# Farmduino_b_ta.net
KiCad netlist of a schematic drawn in EAGLE
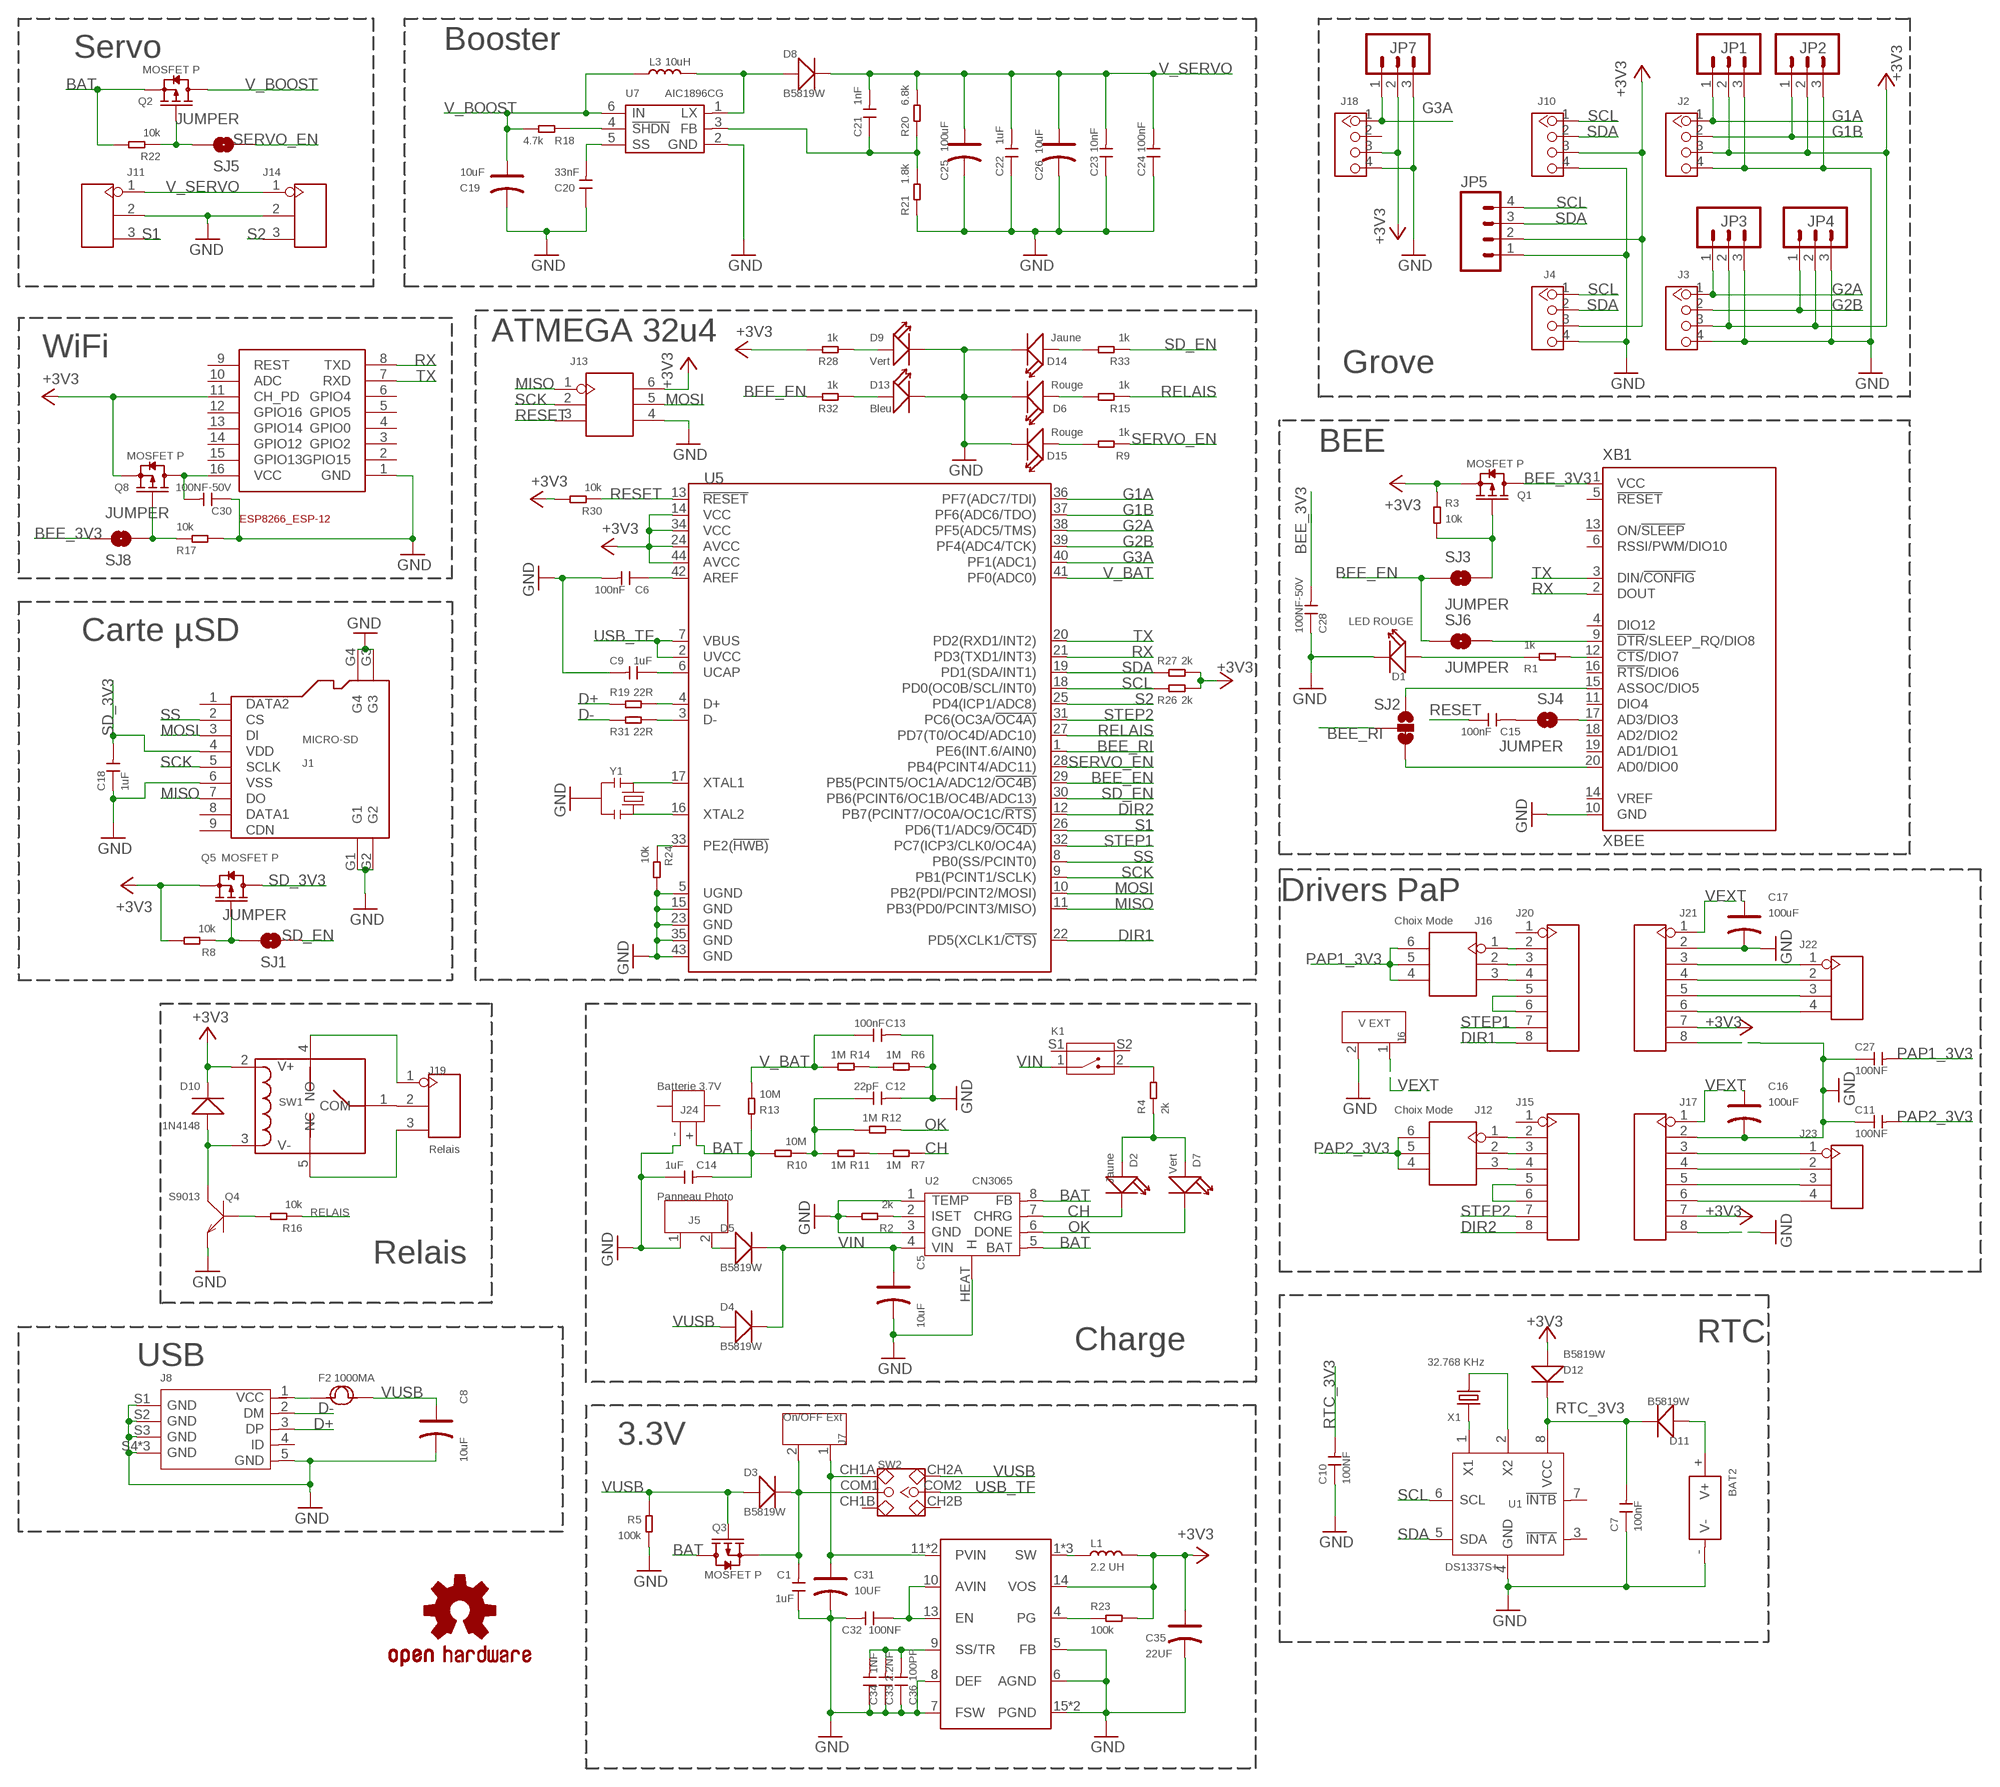
[diagram p0: schematic, sheet 1]

(export (version "E")
  (design (tool "Eeschema 10.0.6"))
  (components
    (comp (ref "BAT2")
      (value "SMD-BATTERY-CELL-HOLDER-PLASTIC")
      (footprint "eagle-import:BAT2P-SMD-16.4-CR1220")
      (libsource (lib "eagle-import") (part "SMD-BATTERY-CELL-HOLDER-PLASTIC"))
    )
    (comp (ref "C1")
      (value "1uF")
      (footprint "eagle-import:C0805")
      (fields
        (field (name "MPN") "CC0805KKX7R8BB105")
        (field (name "MF") "AVX")
        (field (name "MPN_1") "02016D105MAT2A")
      )
      (libsource (lib "eagle-import") (part "CERAMIC-1UF-25V-10%-X7R(0805)"))
    )
    (comp (ref "C5")
      (value "10uF")
      (footprint "eagle-import:AVX-A")
      (fields
        (field (name "MPN") "TAJA106K016RNJ")
        (field (name "MF") "AVX")
        (field (name "MPN_1") "06036D106MAT2A")
      )
      (libsource (lib "eagle-import") (part "TANTALUM-SMD-10UF-16V-10%(AVX-A)"))
    )
    (comp (ref "C6")
      (value "100nF")
      (footprint "eagle-import:C0805")
      (fields
        (field (name "MPN") "CC0805KRX7R9BB104")
        (field (name "MF") "AVX")
        (field (name "MPN_1") "0402ZD104KAT2A")
      )
      (libsource (lib "eagle-import") (part "CERAMIC-100NF-50V-10%-X7R(0805)"))
    )
    (comp (ref "C7")
      (value "100nF")
      (footprint "eagle-import:C0805")
      (fields
        (field (name "MPN") "CC0805KRX7R9BB104")
        (field (name "MF") "AVX")
        (field (name "MPN_1") "0402ZD104KAT2A")
      )
      (libsource (lib "eagle-import") (part "CERAMIC-100NF-50V-10%-X7R(0805)"))
    )
    (comp (ref "C8")
      (value "10uF")
      (footprint "eagle-import:AVX-A")
      (fields
        (field (name "MPN") "TAJA106K016RNJ")
        (field (name "MF") "AVX")
        (field (name "MPN_1") "06036D106MAT2A")
      )
      (libsource (lib "eagle-import") (part "TANTALUM-SMD-10UF-16V-10%(AVX-A)"))
    )
    (comp (ref "C9")
      (value "1uF")
      (footprint "eagle-import:C0805")
      (fields (field (name "MPN") "CC0805KKX7R8BB105") (field (name "MF") "AVX"))
      (libsource (lib "eagle-import") (part "CERAMIC-1UF-25V-10%-X7R(0805)"))
    )
    (comp (ref "C10")
      (value "100NF")
      (footprint "eagle-import:C0805")
      (fields (field (name "MPN") "CC0805KRX7R9BB104"))
      (libsource (lib "eagle-import") (part "CERAMIC-100NF-50V-10%-X7R(0805)"))
    )
    (comp (ref "C11")
      (value "100NF")
      (footprint "eagle-import:C0805")
      (fields (field (name "MPN") "CC0805KRX7R9BB104"))
      (libsource (lib "eagle-import") (part "CERAMIC-100NF-50V-10%-X7R(0805)"))
    )
    (comp (ref "C12")
      (value "22pF")
      (footprint "eagle-import:C0805")
      (fields (field (name "MPN") "CC0805JRNPO9BN220"))
      (libsource (lib "eagle-import") (part "CERAMIC-22PF-50V-5%-NPO(0805)"))
    )
    (comp (ref "C13")
      (value "100nF")
      (footprint "eagle-import:C0805")
      (fields
        (field (name "MPN") "CC0805KRX7R9BB104")
        (field (name "MF") "AVX")
        (field (name "MPN_1") "0402ZD104KAT2A")
      )
      (libsource (lib "eagle-import") (part "CERAMIC-100NF-50V-10%-X7R(0805)"))
    )
    (comp (ref "C14")
      (value "1uF")
      (footprint "eagle-import:C0805")
      (fields
        (field (name "MPN") "CC0805KKX7R8BB105")
        (field (name "MF") "AVX")
        (field (name "MPN_1") "02016D105MAT2A")
      )
      (libsource (lib "eagle-import") (part "CERAMIC-1UF-25V-10%-X7R(0805)"))
    )
    (comp (ref "C15")
      (value "100nF")
      (footprint "eagle-import:C0805")
      (fields
        (field (name "MPN") "CC0805KRX7R9BB104")
        (field (name "MF") "AVX")
        (field (name "MPN_1") "0402ZD104KAT2A")
      )
      (libsource (lib "eagle-import") (part "CERAMIC-100NF-50V-10%-X7R(0805)"))
    )
    (comp (ref "C16")
      (value "100uF")
      (footprint "eagle-import:ELECTRO-SMD-C-6MM")
      (fields
        (field (name "MPN") "CS1H101M-CRE77")
        (field (name "MF") "AVX")
        (field (name "MPN_1") "06036D106MAT2A")
      )
      (libsource (lib "eagle-import") (part "ALUMINUM-SMD-100UF-50V-20%"))
    )
    (comp (ref "C17")
      (value "100uF")
      (footprint "eagle-import:ELECTRO-SMD-C-6MM")
      (fields
        (field (name "MPN") "CS1H101M-CRE77")
        (field (name "MF") "AVX")
        (field (name "MPN_1") "06036D106MAT2A")
      )
      (libsource (lib "eagle-import") (part "ALUMINUM-SMD-100UF-50V-20%"))
    )
    (comp (ref "C18")
      (value "1uF")
      (footprint "eagle-import:C0805")
      (fields
        (field (name "MPN") "CC0805KKX7R8BB105")
        (field (name "MF") "AVX")
        (field (name "MPN_1") "02016D105MAT2A")
      )
      (libsource (lib "eagle-import") (part "CERAMIC-1UF-25V-10%-X7R(0805)"))
    )
    (comp (ref "C19")
      (value "10uF")
      (footprint "eagle-import:AVX-A")
      (fields (field (name "MPN") "TAJA106K010RNJ"))
      (libsource (lib "eagle-import") (part "TANTALUM-SMD-10UF-10V-10%(AVX-A)"))
    )
    (comp (ref "C20")
      (value "33nF")
      (footprint "eagle-import:C0603")
      (fields (field (name "MPN") "CC0603KRX7R9BB333"))
      (libsource (lib "eagle-import") (part "CERAMIC-33NF-50V-10%-X7R(0603)"))
    )
    (comp (ref "C21")
      (value "1nF")
      (footprint "eagle-import:C0603")
      (fields (field (name "MPN") "GRM1885C1H102JA01D"))
      (libsource (lib "eagle-import") (part "CERAMIC-1NF-50V-5%-C0G(0603)"))
    )
    (comp (ref "C22")
      (value "1uF")
      (footprint "eagle-import:C0805")
      (fields
        (field (name "MPN") "CC0805KKX7R8BB105")
        (field (name "MF") "AVX")
        (field (name "MPN_1") "02016D105MAT2A")
      )
      (libsource (lib "eagle-import") (part "CERAMIC-1UF-25V-10%-X7R(0805)"))
    )
    (comp (ref "C23")
      (value "10nF")
      (footprint "eagle-import:C0805")
      (fields (field (name "MPN") "CC0805JRX7R9BB103"))
      (libsource (lib "eagle-import") (part "CERAMIC-10NF-50V-5%-X7R(0805)"))
    )
    (comp (ref "C24")
      (value "100nF")
      (footprint "eagle-import:C0805")
      (fields
        (field (name "MPN") "CC0805KRX7R9BB104")
        (field (name "MF") "AVX")
        (field (name "MPN_1") "0402ZD104KAT2A")
      )
      (libsource (lib "eagle-import") (part "CERAMIC-100NF-50V-10%-X7R(0805)"))
    )
    (comp (ref "C25")
      (value "100uF")
      (footprint "eagle-import:AVX-B")
      (fields (field (name "MPN") "TAJB107M010#NJ"))
      (libsource (lib "eagle-import") (part "TANTALUM-SMD-100UF-10V(AVX-B)"))
    )
    (comp (ref "C26")
      (value "10uF")
      (footprint "eagle-import:AVX-A")
      (fields (field (name "MPN") "TAJA106K016RNJ"))
      (libsource (lib "eagle-import") (part "TANTALUM-SMD-10UF-16V-10%(AVX-A)"))
    )
    (comp (ref "C27")
      (value "100NF")
      (footprint "eagle-import:C0805")
      (fields (field (name "MPN") "CC0805KRX7R9BB104"))
      (libsource (lib "eagle-import") (part "CERAMIC-100NF-50V-10%-X7R(0805)"))
    )
    (comp (ref "C28")
      (value "100NF-50V")
      (footprint "eagle-import:C0805")
      (fields (field (name "MPN") "CC0805KRX7R9BB104"))
      (libsource (lib "eagle-import") (part "CERAMIC-100NF-50V-10%-X7R(0805)"))
    )
    (comp (ref "C30")
      (value "100NF-50V")
      (footprint "eagle-import:C0805")
      (fields (field (name "MPN") "CC0805KRX7R9BB104"))
      (libsource (lib "eagle-import") (part "CERAMIC-100NF-50V-10%-X7R(0805)"))
    )
    (comp (ref "C31")
      (value "10UF")
      (footprint "eagle-import:AVX-A")
      (fields (field (name "MPN") "TAJA106K016RNJ"))
      (libsource (lib "eagle-import") (part "TANTALUM-SMD-10UF-16V-10%(AVX-A)"))
    )
    (comp (ref "C32")
      (value "100NF")
      (footprint "eagle-import:C0805")
      (fields (field (name "MPN") "CC0805KRX7R9BB104"))
      (libsource (lib "eagle-import") (part "CERAMIC-100NF-50V-10%-X7R(0805)"))
    )
    (comp (ref "C33")
      (value "2.2NF")
      (footprint "eagle-import:C0603")
      (fields (field (name "MPN") "CC0603KRX7R9BB222"))
      (libsource (lib "eagle-import") (part "CERAMIC-2.2NF-50V-10%-X7R(0603)"))
    )
    (comp (ref "C34")
      (value "1NF")
      (footprint "eagle-import:C0603")
      (fields (field (name "MPN") "GRM1885C1H102JA01D"))
      (libsource (lib "eagle-import") (part "CERAMIC-1NF-50V-5%-C0G(0603)"))
    )
    (comp (ref "C35")
      (value "22UF")
      (footprint "eagle-import:AVX-B")
      (fields (field (name "MPN") "TAJB226*016#NJ"))
      (libsource (lib "eagle-import") (part "TANTALUM-SMD-22UF-16V(AVX-B)"))
    )
    (comp (ref "C36")
      (value "100PF")
      (footprint "eagle-import:C0603")
      (libsource (lib "eagle-import") (part "CERAMIC-100PF-50V-5%-NPO(0603)"))
    )
    (comp (ref "D1")
      (value "LED ROUGE")
      (footprint "eagle-import:LED-0603")
      (fields (field (name "MPN") "19-217-R6C-AL1M2VY-3T"))
      (libsource (lib "eagle-import") (part "LED-SMD-RED-DIFFUSED(0603)"))
    )
    (comp (ref "D2")
      (value "Jaune")
      (footprint "eagle-import:LED-0805")
      (fields (field (name "MPN") "17-215UYC/S530-A3/TR8"))
      (libsource (lib "eagle-import") (part "SMD-LED-CLEAR-YELLOW(0805)"))
    )
    (comp (ref "D3")
      (value "B5819W")
      (footprint "eagle-import:SOD-123")
      (libsource (lib "eagle-import") (part "SMD-DIODE-SCHOTTKY-20V-1A(SOD-123)"))
    )
    (comp (ref "D4")
      (value "B5819W")
      (footprint "eagle-import:SOD-123")
      (libsource (lib "eagle-import") (part "SMD-DIODE-SCHOTTKY-20V-1A(SOD-123)"))
    )
    (comp (ref "D5")
      (value "B5819W")
      (footprint "eagle-import:SOD-123")
      (libsource (lib "eagle-import") (part "SMD-DIODE-SCHOTTKY-20V-1A(SOD-123)"))
    )
    (comp (ref "D6")
      (value "Rouge")
      (footprint "eagle-import:LED-0603")
      (fields (field (name "MPN") "19-217-R6C-AL1M2VY-3T"))
      (libsource (lib "eagle-import") (part "LED-SMD-RED-DIFFUSED(0603)"))
    )
    (comp (ref "D7")
      (value "Vert")
      (footprint "eagle-import:LED-0805")
      (fields (field (name "MPN") "17-215SYGC/S530-E2/TR8"))
      (libsource (lib "eagle-import") (part "SMD-LED-CLEAR-GREEN(0805)"))
    )
    (comp (ref "D8")
      (value "B5819W")
      (footprint "eagle-import:SOD-123")
      (libsource (lib "eagle-import") (part "SMD-DIODE-SCHOTTKY-20V-1A(SOD-123)"))
    )
    (comp (ref "D9")
      (value "Vert")
      (footprint "eagle-import:LED-0603")
      (fields (field (name "MPN") "19-217-G7C-AN1P2-3T"))
      (libsource (lib "eagle-import") (part "SMD-LED-CLEAR-GREEN(0603)"))
    )
    (comp (ref "D10")
      (value "1N4148")
      (footprint "eagle-import:LL-34")
      (libsource (lib "eagle-import") (part "SMD-DIODE-SWITCH-1N4148(LL-34)"))
    )
    (comp (ref "D11")
      (value "B5819W")
      (footprint "eagle-import:SOD-123")
      (libsource (lib "eagle-import") (part "SMD-DIODE-SCHOTTKY-20V-1A(SOD-123)"))
    )
    (comp (ref "D12")
      (value "B5819W")
      (footprint "eagle-import:SOD-123")
      (libsource (lib "eagle-import") (part "SMD-DIODE-SCHOTTKY-20V-1A(SOD-123)"))
    )
    (comp (ref "D13")
      (value "Bleu")
      (footprint "eagle-import:LED-0603")
      (fields (field (name "MPN") "19-217-BHC-ZL1M2RY-3T"))
      (libsource (lib "eagle-import") (part "SMD-LED-CLEAR-BLUE(0603)"))
    )
    (comp (ref "D14")
      (value "Jaune")
      (footprint "eagle-import:LED-0603")
      (fields (field (name "MPN") "19-217-Y5C-AM1N1VY-3T"))
      (libsource (lib "eagle-import") (part "SMD-LED-CLEAR-YELLOW(0603)"))
    )
    (comp (ref "D15")
      (value "Rouge")
      (footprint "eagle-import:LED-0603")
      (fields (field (name "MPN") "19-217-R6C-AL1M2VY-3T"))
      (libsource (lib "eagle-import") (part "LED-SMD-RED-DIFFUSED(0603)"))
    )
    (comp (ref "F2")
      (value "1000MA")
      (footprint "eagle-import:F1206")
      (fields (field (name "MPN") "KT8-1000SMD1206"))
      (libsource (lib "eagle-import") (part "SMD-PPTC-1000MA-8V(1206)"))
    )
    (comp (ref "J1")
      (value "MICRO-SD")
      (footprint "eagle-import:MICRO-SD9+4P-SMD-16.1X14.5X1.85MM")
      (fields (field (name "MPN") "ST-TF-003A"))
      (libsource (lib "eagle-import") (part "MICRO-SD-CARD-SOCKET-9P(ST-TF-003A)"))
    )
    (comp (ref "J2")
      (value "GROVE-CONNECTOR-DIP(4P-2.0)")
      (footprint "eagle-import:HW4-2.0")
      (libsource (lib "eagle-import") (part "GROVE-CONNECTOR-DIP(4P-2.0)"))
    )
    (comp (ref "J3")
      (value "GROVE-CONNECTOR-DIP(4P-2.0)")
      (footprint "eagle-import:HW4-2.0")
      (libsource (lib "eagle-import") (part "GROVE-CONNECTOR-DIP(4P-2.0)"))
    )
    (comp (ref "J4")
      (value "GROVE-CONNECTOR-DIP(4P-2.0)")
      (footprint "eagle-import:HW4-2.0")
      (libsource (lib "eagle-import") (part "GROVE-CONNECTOR-DIP(4P-2.0)"))
    )
    (comp (ref "J5")
      (value "Panneau Photo")
      (footprint "eagle-import:H2-3.5-7.0X7.0MM")
      (fields (field (name "MF") "TE CONNECTIVITY") (field (name "MPN") "1776275-2"))
      (libsource (lib "eagle-import") (part "SCREW-TERMINAL-GREEN(2P-3.5)"))
    )
    (comp (ref "J6")
      (value "V EXT")
      (footprint "eagle-import:H2-3.5-7.0X7.0MM")
      (fields (field (name "MF") "TE CONNECTIVITY") (field (name "MPN") "1776275-2"))
      (libsource (lib "eagle-import") (part "SCREW-TERMINAL-GREEN(2P-3.5)"))
    )
    (comp (ref "J7")
      (value "On/OFF Ext")
      (footprint "eagle-import:H2-3.5-7.0X7.0MM")
      (libsource (lib "eagle-import") (part "SCREW-TERMINAL-GREEN(2P-3.5)"))
    )
    (comp (ref "J8")
      (value "MICRO-USB-SMD-B-WITHOUT-POST-W/P(ST-USB-001G)")
      (footprint "eagle-import:MICRO-USB5+4P-SMD-0.65-B")
      (fields (field (name "MPN") "ST-USB-001G"))
      (libsource (lib "eagle-import") (part "MICRO-USB-SMD-B-WITHOUT-POST-W/P(ST-USB-001G)"))
    )
    (comp (ref "J10")
      (value "GROVE-CONNECTOR-DIP(4P-2.0)")
      (footprint "eagle-import:HW4-2.0")
      (libsource (lib "eagle-import") (part "GROVE-CONNECTOR-DIP(4P-2.0)"))
    )
    (comp (ref "J11")
      (value "DIP-WHITE-MALE-HEADER-VERT(3P-2.54)")
      (footprint "eagle-import:H3-2.54")
      (fields (field (name "MPN") "P125-1103A0BS116A1"))
      (libsource (lib "eagle-import") (part "DIP-WHITE-MALE-HEADER-VERT(3P-2.54)"))
    )
    (comp (ref "J12")
      (value "Choix Mode")
      (footprint "eagle-import:H2X3-2.54")
      (fields (field (name "MPN") "P125-1203A0BS116A2"))
      (libsource (lib "eagle-import") (part "DIP-YELLOW-MALE-HEADER-VERT(2X3P-2.54)"))
    )
    (comp (ref "J13")
      (value "DIP-BLACK-MALE-HEADER（2X3P-2.54）-2.54")
      (footprint "eagle-import:H2X3-2.54")
      (fields (field (name "MPN") "P125-12A1BS116A1"))
      (libsource (lib "eagle-import") (part "DIP-BLACK-MALE-HEADER（2X3P-2.54）-2.54"))
    )
    (comp (ref "J14")
      (value "DIP-WHITE-MALE-HEADER-VERT(3P-2.54)")
      (footprint "eagle-import:H3-2.54")
      (fields (field (name "MPN") "P125-1103A0BS116A1"))
      (libsource (lib "eagle-import") (part "DIP-WHITE-MALE-HEADER-VERT(3P-2.54)"))
    )
    (comp (ref "J15")
      (value "DIP-YELLOW-FEMALE-HEADER(8P-2.54)")
      (footprint "eagle-import:H8-2.54")
      (fields (field (name "MPN") "F185-1108A1BSYC1"))
      (libsource (lib "eagle-import") (part "DIP-YELLOW-FEMALE-HEADER(8P-2.54)"))
    )
    (comp (ref "J16")
      (value "Choix Mode")
      (footprint "eagle-import:H2X3-2.54")
      (fields (field (name "MPN") "P125-1203A0BS116A2"))
      (libsource (lib "eagle-import") (part "DIP-YELLOW-MALE-HEADER-VERT(2X3P-2.54)"))
    )
    (comp (ref "J17")
      (value "DIP-YELLOW-FEMALE-HEADER(8P-2.54)")
      (footprint "eagle-import:H8-2.54")
      (fields (field (name "MPN") "F185-1108A1BSYC1"))
      (libsource (lib "eagle-import") (part "DIP-YELLOW-FEMALE-HEADER(8P-2.54)"))
    )
    (comp (ref "J18")
      (value "GROVE-CONNECTOR-DIP(4P-2.0)")
      (footprint "eagle-import:HW4-2.0")
      (libsource (lib "eagle-import") (part "GROVE-CONNECTOR-DIP(4P-2.0)"))
    )
    (comp (ref "J19")
      (value "Relais")
      (footprint "eagle-import:H3-5.0-15.5X8.0MM")
      (libsource (lib "eagle-import") (part "SCREW-TERMINAL-GREEN(3P-5.0)"))
    )
    (comp (ref "J20")
      (value "DIP-YELLOW-FEMALE-HEADER(8P-2.54)")
      (footprint "eagle-import:H8-2.54")
      (fields (field (name "MPN") "F185-1108A1BSYC1"))
      (libsource (lib "eagle-import") (part "DIP-YELLOW-FEMALE-HEADER(8P-2.54)"))
    )
    (comp (ref "J21")
      (value "DIP-YELLOW-FEMALE-HEADER(8P-2.54)")
      (footprint "eagle-import:H8-2.54")
      (fields (field (name "MPN") "F185-1108A1BSYC1"))
      (libsource (lib "eagle-import") (part "DIP-YELLOW-FEMALE-HEADER(8P-2.54)"))
    )
    (comp (ref "J22")
      (value "DIP-BLACK-MALE-HEADER-VERT(4P-2.54)")
      (footprint "eagle-import:H4-2.54")
      (fields (field (name "MPN") "P125-1104A0BS116A1"))
      (libsource (lib "eagle-import") (part "DIP-BLACK-MALE-HEADER-VERT(4P-2.54)"))
    )
    (comp (ref "J23")
      (value "DIP-BLACK-MALE-HEADER-VERT(4P-2.54)")
      (footprint "eagle-import:H4-2.54")
      (fields (field (name "MPN") "P125-1104A0BS116A1"))
      (libsource (lib "eagle-import") (part "DIP-BLACK-MALE-HEADER-VERT(4P-2.54)"))
    )
    (comp (ref "J24")
      (value "Batterie 3.7V")
      (footprint "eagle-import:HW2-SMD-1.0-90D")
      (libsource (lib "eagle-import") (part "SMD-JST-2P-1.0-90D"))
    )
    (comp (ref "JP1")
      (value "M03SCREW")
      (footprint "eagle-import:SCREWTERMINAL-3.5MM-3")
      (libsource (lib "eagle-import") (part "M03SCREW"))
    )
    (comp (ref "JP2")
      (value "M03SCREW")
      (footprint "eagle-import:SCREWTERMINAL-3.5MM-3")
      (libsource (lib "eagle-import") (part "M03SCREW"))
    )
    (comp (ref "JP3")
      (value "M03SCREW")
      (footprint "eagle-import:SCREWTERMINAL-3.5MM-3")
      (libsource (lib "eagle-import") (part "M03SCREW"))
    )
    (comp (ref "JP4")
      (value "M03SCREW")
      (footprint "eagle-import:SCREWTERMINAL-3.5MM-3")
      (libsource (lib "eagle-import") (part "M03SCREW"))
    )
    (comp (ref "JP5")
      (value "M04SCREW")
      (footprint "eagle-import:SCREWTERMINAL-3.5MM-4")
      (libsource (lib "eagle-import") (part "M04SCREW"))
    )
    (comp (ref "JP7")
      (value "M03SCREW")
      (footprint "eagle-import:SCREWTERMINAL-3.5MM-3")
      (libsource (lib "eagle-import") (part "M03SCREW"))
    )
    (comp (ref "K1")
      (value "SMD-BUTTON-2+2P")
      (footprint "eagle-import:SW4-SMD-7.0X3.5X3.5MM-90D")
      (fields (field (name "MPN") "TS-1188E"))
      (libsource (lib "eagle-import") (part "SMD-BUTTON-2+2P"))
    )
    (comp (ref "L1")
      (value "2.2 UH")
      (footprint "eagle-import:L0805")
      (fields (field (name "MPN") "LQM2MPN2R2MG0"))
      (libsource (lib "eagle-import") (part "SMD-INDUCTOR-2.2UH-20%-1.2A(0805)"))
    )
    (comp (ref "L3")
      (value "10uH")
      (footprint "eagle-import:L1210")
      (fields (field (name "MPN") "CBC3225T100MR"))
      (libsource (lib "eagle-import") (part "SMD-INDUCTOR-10UH-20%-900MA(L1210)"))
    )
    (comp (ref "LOGO1")
      (value "OSHW-LOGOM")
      (footprint "eagle-import:OSHW-LOGO-M")
      (libsource (lib "eagle-import") (part "OSHW-LOGOM"))
    )
    (comp (ref "Q1")
      (value "MOSFET P")
      (footprint "eagle-import:SOT-23")
      (fields (field (name "MPN") "CJ2305"))
      (libsource (lib "eagle-import") (part "SMD-MOSFET-P-CH-8V-4.1A(SOT-23)"))
    )
    (comp (ref "Q2")
      (value "MOSFET P")
      (footprint "eagle-import:SOT-23")
      (fields (field (name "MPN") "CJ2305"))
      (libsource (lib "eagle-import") (part "SMD-MOSFET-P-CH-8V-4.1A(SOT-23)"))
    )
    (comp (ref "Q3")
      (value "MOSFET P")
      (footprint "eagle-import:SOT-23")
      (fields (field (name "MPN") "CJ2305"))
      (libsource (lib "eagle-import") (part "SMD-MOSFET-P-CH-8V-4.1A(SOT-23)"))
    )
    (comp (ref "Q4")
      (value "S9013")
      (footprint "eagle-import:SOT-23")
      (libsource (lib "eagle-import") (part "SMD-TRANSISTORS-NPN-25V-500MA(SOT-23)"))
    )
    (comp (ref "Q5")
      (value "MOSFET P")
      (footprint "eagle-import:SOT-23")
      (fields (field (name "MPN") "CJ2305"))
      (libsource (lib "eagle-import") (part "SMD-MOSFET-P-CH-8V-4.1A(SOT-23)"))
    )
    (comp (ref "Q8")
      (value "MOSFET P")
      (footprint "eagle-import:SOT-23")
      (fields (field (name "MPN") "CJ2305"))
      (libsource (lib "eagle-import") (part "SMD-MOSFET-P-CH-8V-4.1A(SOT-23)"))
    )
    (comp (ref "R1")
      (value "1k")
      (footprint "eagle-import:R0805")
      (fields (field (name "MPN") "RC0805JR-071KL") (field (name "MF") "STEINBACH AND VOLLMANN"))
      (libsource (lib "eagle-import") (part "SMD-RES-1K-5%-1/8W(0805)"))
    )
    (comp (ref "R2")
      (value "2k")
      (footprint "eagle-import:R0805")
      (fields (field (name "MPN") "RC0805JR-072KL"))
      (libsource (lib "eagle-import") (part "SMD-RES-2K-5%-1/8W(0805)"))
    )
    (comp (ref "R3")
      (value "10k")
      (footprint "eagle-import:R0805")
      (fields (field (name "MPN") "RC0805FR-0710KL") (field (name "MF") "STEINBACH AND VOLLMANN"))
      (libsource (lib "eagle-import") (part "SMD-RES-10K-1%-1/8W(0805)"))
    )
    (comp (ref "R4")
      (value "2k")
      (footprint "eagle-import:R0805")
      (fields (field (name "MPN") "RC0805JR-072KL"))
      (libsource (lib "eagle-import") (part "SMD-RES-2K-5%-1/8W(0805)"))
    )
    (comp (ref "R5")
      (value "100k")
      (footprint "eagle-import:R0805")
      (fields (field (name "MPN") "RC0805FR-07100KL"))
      (libsource (lib "eagle-import") (part "SMD-RES-100K-1%-1/8W(0805)"))
    )
    (comp (ref "R6")
      (value "1M")
      (footprint "eagle-import:R0402")
      (fields (field (name "MPN") "RC0402FR-071ML"))
      (libsource (lib "eagle-import") (part "SMD-RES-1M-1%-1/16W(0402)"))
    )
    (comp (ref "R7")
      (value "1M")
      (footprint "eagle-import:R0402")
      (fields (field (name "MPN") "RC0402FR-071ML"))
      (libsource (lib "eagle-import") (part "SMD-RES-1M-1%-1/16W(0402)"))
    )
    (comp (ref "R8")
      (value "10k")
      (footprint "eagle-import:R0805")
      (fields (field (name "MPN") "RC0805FR-0710KL"))
      (libsource (lib "eagle-import") (part "SMD-RES-10K-1%-1/8W(0805)"))
    )
    (comp (ref "R9")
      (value "1k")
      (footprint "eagle-import:R0805")
      (fields (field (name "MPN") "RC0805JR-071KL") (field (name "MF") "STEINBACH AND VOLLMANN"))
      (libsource (lib "eagle-import") (part "SMD-RES-1K-5%-1/8W(0805)"))
    )
    (comp (ref "R10")
      (value "10M")
      (footprint "eagle-import:R0603")
      (fields (field (name "MPN") "RC0603FR-0710ML"))
      (libsource (lib "eagle-import") (part "SMD-RES-10M-1%-1/10W(0603)"))
    )
    (comp (ref "R11")
      (value "1M")
      (footprint "eagle-import:R0402")
      (fields (field (name "MPN") "RC0402FR-071ML"))
      (libsource (lib "eagle-import") (part "SMD-RES-1M-1%-1/16W(0402)"))
    )
    (comp (ref "R12")
      (value "1M")
      (footprint "eagle-import:R0805")
      (fields (field (name "MPN") "RC0805JR-071ML"))
      (libsource (lib "eagle-import") (part "SMD-RES-1M-5%-1/8W(0805)"))
    )
    (comp (ref "R13")
      (value "10M")
      (footprint "eagle-import:R0603")
      (fields (field (name "MPN") "RC0603FR-0710ML"))
      (libsource (lib "eagle-import") (part "SMD-RES-10M-1%-1/10W(0603)"))
    )
    (comp (ref "R14")
      (value "1M")
      (footprint "eagle-import:R0402")
      (fields (field (name "MPN") "RC0402FR-071ML"))
      (libsource (lib "eagle-import") (part "SMD-RES-1M-1%-1/16W(0402)"))
    )
    (comp (ref "R15")
      (value "1k")
      (footprint "eagle-import:R0805")
      (fields (field (name "MPN") "RC0805JR-071KL") (field (name "MF") "STEINBACH AND VOLLMANN"))
      (libsource (lib "eagle-import") (part "SMD-RES-1K-5%-1/8W(0805)"))
    )
    (comp (ref "R16")
      (value "10k")
      (footprint "eagle-import:R0805")
      (fields (field (name "MPN") "RC0805FR-0710KL"))
      (libsource (lib "eagle-import") (part "SMD-RES-10K-1%-1/8W(0805)"))
    )
    (comp (ref "R17")
      (value "10k")
      (footprint "eagle-import:R0805")
      (fields (field (name "MPN") "RC0805FR-0710KL"))
      (libsource (lib "eagle-import") (part "SMD-RES-10K-1%-1/8W(0805)"))
    )
    (comp (ref "R18")
      (value "4.7k")
      (footprint "eagle-import:R0805")
      (fields (field (name "MPN") "RC0805JR-074K7L"))
      (libsource (lib "eagle-import") (part "SMD-RES-4.7K-5%-1/8W(0805)"))
    )
    (comp (ref "R19")
      (value "22R")
      (footprint "eagle-import:R0805")
      (fields (field (name "MPN") "RC0805JR-0722RL"))
      (libsource (lib "eagle-import") (part "SMD-RES-22R-5%-1/8W(0805)"))
    )
    (comp (ref "R20")
      (value "6.8k")
      (footprint "eagle-import:R0603")
      (fields (field (name "MPN") "RC0805JR-07220KL"))
      (libsource (lib "eagle-import") (part "SMD-RES-6.8K-1%-1/10W(0603)"))
    )
    (comp (ref "R21")
      (value "1.8k")
      (footprint "eagle-import:R0603")
      (fields (field (name "MPN") "RC0603FR-071K8L"))
      (libsource (lib "eagle-import") (part "SMD-RES-1.8K-1%-1/10W(0603)"))
    )
    (comp (ref "R22")
      (value "10k")
      (footprint "eagle-import:R0805")
      (fields (field (name "MPN") "RC0805FR-0710KL"))
      (libsource (lib "eagle-import") (part "SMD-RES-10K-1%-1/8W(0805)"))
    )
    (comp (ref "R23")
      (value "100k")
      (footprint "eagle-import:R0805")
      (fields (field (name "MPN") "RC0805FR-07100KL"))
      (libsource (lib "eagle-import") (part "SMD-RES-100K-1%-1/8W(0805)"))
    )
    (comp (ref "R24")
      (value "10k")
      (footprint "eagle-import:R0805")
      (fields (field (name "MPN") "RC0805FR-0710KL") (field (name "MF") "STEINBACH AND VOLLMANN"))
      (libsource (lib "eagle-import") (part "SMD-RES-10K-1%-1/8W(0805)"))
    )
    (comp (ref "R26")
      (value "2k")
      (footprint "eagle-import:R0603")
      (fields (field (name "MPN") "RC0603JR-072KL"))
      (libsource (lib "eagle-import") (part "SMD-RES-2K-5%-1/10W(0603)"))
    )
    (comp (ref "R27")
      (value "2k")
      (footprint "eagle-import:R0805")
      (fields (field (name "MPN") "RC0805JR-072KL"))
      (libsource (lib "eagle-import") (part "SMD-RES-2K-5%-1/8W(0805)"))
    )
    (comp (ref "R28")
      (value "1k")
      (footprint "eagle-import:R0805")
      (fields (field (name "MPN") "RC0805JR-071KL") (field (name "MF") "STEINBACH AND VOLLMANN"))
      (libsource (lib "eagle-import") (part "SMD-RES-1K-5%-1/8W(0805)"))
    )
    (comp (ref "R30")
      (value "10k")
      (footprint "eagle-import:R0805")
      (fields (field (name "MPN") "RC0805FR-0710KL") (field (name "MF") "STEINBACH AND VOLLMANN"))
      (libsource (lib "eagle-import") (part "SMD-RES-10K-1%-1/8W(0805)"))
    )
    (comp (ref "R31")
      (value "22R")
      (footprint "eagle-import:R0805")
      (fields (field (name "MPN") "RC0805JR-0722RL"))
      (libsource (lib "eagle-import") (part "SMD-RES-22R-5%-1/8W(0805)"))
    )
    (comp (ref "R32")
      (value "1k")
      (footprint "eagle-import:R0805")
      (fields (field (name "MPN") "RC0805JR-071KL") (field (name "MF") "STEINBACH AND VOLLMANN"))
      (libsource (lib "eagle-import") (part "SMD-RES-1K-5%-1/8W(0805)"))
    )
    (comp (ref "R33")
      (value "1k")
      (footprint "eagle-import:R0805")
      (fields (field (name "MPN") "RC0805JR-071KL") (field (name "MF") "STEINBACH AND VOLLMANN"))
      (libsource (lib "eagle-import") (part "SMD-RES-1K-5%-1/8W(0805)"))
    )
    (comp (ref "SJ1")
      (value "JUMPER")
      (footprint "eagle-import:PAD-JUMPER-2-NO_NO_SILK")
      (libsource (lib "eagle-import") (part "JUMPER-PAD-2-NO"))
    )
    (comp (ref "SJ2")
      (value "JUMPER-PAD-3-2OF3_NC_BY_TRACE_LARGE")
      (footprint "eagle-import:PAD-JUMPER-3-2OF3_NC_BY_TRACE_YES_SILK_LARGE")
      (libsource (lib "eagle-import") (part "JUMPER-PAD-3-2OF3_NC_BY_TRACE_LARGE"))
    )
    (comp (ref "SJ3")
      (value "JUMPER")
      (footprint "eagle-import:PAD-JUMPER-2-NO_NO_SILK")
      (libsource (lib "eagle-import") (part "JUMPER-PAD-2-NO"))
    )
    (comp (ref "SJ4")
      (value "JUMPER")
      (footprint "eagle-import:PAD-JUMPER-2-NO_NO_SILK")
      (libsource (lib "eagle-import") (part "JUMPER-PAD-2-NO"))
    )
    (comp (ref "SJ5")
      (value "JUMPER")
      (footprint "eagle-import:PAD-JUMPER-2-NO_NO_SILK")
      (libsource (lib "eagle-import") (part "JUMPER-PAD-2-NO"))
    )
    (comp (ref "SJ6")
      (value "JUMPER")
      (footprint "eagle-import:PAD-JUMPER-2-NO_NO_SILK")
      (libsource (lib "eagle-import") (part "JUMPER-PAD-2-NO"))
    )
    (comp (ref "SJ8")
      (value "JUMPER")
      (footprint "eagle-import:PAD-JUMPER-2-NO_NO_SILK")
      (libsource (lib "eagle-import") (part "JUMPER-PAD-2-NO"))
    )
    (comp (ref "SW1")
      (value "RELAY-HLS8L-DC3V-S-C(5P-19X15MM)")
      (footprint "eagle-import:REY5-19.0X15.0X15.0MM")
      (libsource (lib "eagle-import") (part "RELAY-HLS8L-DC3V-S-C(5P-19X15MM)"))
    )
    (comp (ref "SW2")
      (value "DIP-TOGGLE-SWITCH-2CH-(2X3P-90D)")
      (footprint "eagle-import:SW6-2.54-9.0X3.5X3.2MM-90D")
      (fields (field (name "MPN") "MS-22D18-G2"))
      (libsource (lib "eagle-import") (part "DIP-TOGGLE-SWITCH-2CH-(2X3P-90D)"))
    )
    (comp (ref "U$1")
      (value "ESP8266_ESP-12")
      (footprint "eagle-import:ESP8266-ESP12")
      (libsource (lib "eagle-import") (part "ESP8266_ESP-12"))
    )
    (comp (ref "U1")
      (value "DS1337S+")
      (footprint "eagle-import:SOIC8-1.27-5X4MM")
      (libsource (lib "eagle-import") (part "CLOCK-DS1337S+(SOIC8)"))
    )
    (comp (ref "U2")
      (value "CN3065")
      (footprint "eagle-import:DFN8G-0.5-3X3MM")
      (libsource (lib "eagle-import") (part "PMIC-CN3065(DFN8)"))
    )
    (comp (ref "U3")
      (value "TPS62132RGTR")
      (footprint "eagle-import:QFN16G-0.5-3X3MM")
      (libsource (lib "eagle-import") (part "PMIC-TPS62132RGTR(QFN16)"))
    )
    (comp (ref "U5")
      (value "MCU-ATMEGA32U4(TQFP44)-AU")
      (footprint "eagle-import:TQFP44-0.8-9.6X9.6MM")
      (libsource (lib "eagle-import") (part "MCU-ATMEGA32U4(TQFP44)-AU"))
    )
    (comp (ref "U7")
      (value "AIC1896CG")
      (footprint "eagle-import:SOT-23-6")
      (libsource (lib "eagle-import") (part "PMIC-AIC1896CG(SOT23-6)"))
    )
    (comp (ref "X1")
      (value "32.768 KHz")
      (footprint "eagle-import:X2-SMD-3.2X1.5X0.55MM")
      (fields (field (name "MPN") "FC-135"))
      (libsource (lib "eagle-import") (part "SMD-CRYSTAL-ABS07-32.768KHZ-7PF-20PPM-70K(2P-3.2X1.5MM)"))
    )
    (comp (ref "XB1")
      (value "XBEE")
      (footprint "eagle-import:XBEE")
      (fields (field (name "MPN") "XBP24-Z7UIT-004"))
      (libsource (lib "eagle-import") (part "XBEE"))
    )
    (comp (ref "Y1")
      (value "SMD-CRYSTAL-8MHZ--0.3%-150R(3P-3.6X1.3MM)")
      (footprint "eagle-import:X3-SMD-3.6X1.3X0.8MM")
      (libsource (lib "eagle-import") (part "SMD-CRYSTAL-8MHZ--0.3%-150R(3P-3.6X1.3MM)"))
    )
  )
  (nets
    (net (code "1") (name "+3V3") (class "Default")
      (node (ref "C35") (pin "+") (pinfunction "+_+") (pintype "passive"))
      (node (ref "D10") (pin "C") (pinfunction "-_C") (pintype "passive"))
      (node (ref "D12") (pin "+") (pinfunction "+_+") (pintype "passive"))
      (node (ref "J10") (pin "3") (pinfunction "3_3") (pintype "bidirectional"))
      (node (ref "J13") (pin "6") (pinfunction "6_6") (pintype "bidirectional"))
      (node (ref "J17") (pin "7") (pinfunction "7_7") (pintype "bidirectional"))
      (node (ref "J18") (pin "3") (pinfunction "3_3") (pintype "bidirectional"))
      (node (ref "J2") (pin "3") (pinfunction "3_3") (pintype "bidirectional"))
      (node (ref "J21") (pin "7") (pinfunction "7_7") (pintype "bidirectional"))
      (node (ref "J3") (pin "3") (pinfunction "3_3") (pintype "bidirectional"))
      (node (ref "J4") (pin "3") (pinfunction "3_3") (pintype "bidirectional"))
      (node (ref "JP1") (pin "2") (pinfunction "2_2") (pintype "passive"))
      (node (ref "JP2") (pin "2") (pinfunction "2_2") (pintype "passive"))
      (node (ref "JP3") (pin "2") (pinfunction "2_2") (pintype "passive"))
      (node (ref "JP4") (pin "2") (pinfunction "2_2") (pintype "passive"))
      (node (ref "JP5") (pin "2") (pinfunction "2_2") (pintype "passive"))
      (node (ref "JP7") (pin "2") (pinfunction "2_2") (pintype "passive"))
      (node (ref "L1") (pin "2") (pinfunction "2_2") (pintype "passive"))
      (node (ref "Q1") (pin "2") (pinfunction "S_2") (pintype "passive"))
      (node (ref "Q5") (pin "2") (pinfunction "S_2") (pintype "passive"))
      (node (ref "Q8") (pin "2") (pinfunction "S_2") (pintype "passive"))
      (node (ref "R23") (pin "2") (pinfunction "2_2") (pintype "passive"))
      (node (ref "R26") (pin "1") (pinfunction "1_1") (pintype "passive"))
      (node (ref "R27") (pin "1") (pinfunction "1_1") (pintype "passive"))
      (node (ref "R28") (pin "2") (pinfunction "2_2") (pintype "passive"))
      (node (ref "R3") (pin "1") (pinfunction "1_1") (pintype "passive"))
      (node (ref "R30") (pin "2") (pinfunction "2_2") (pintype "passive"))
      (node (ref "R8") (pin "2") (pinfunction "2_2") (pintype "passive"))
      (node (ref "SW1") (pin "2") (pinfunction "V+_2") (pintype "bidirectional"))
      (node (ref "U$1") (pin "11") (pinfunction "CH_PD_11") (pintype "bidirectional"))
      (node (ref "U3") (pin "14") (pinfunction "VOS_14") (pintype "bidirectional"))
      (node (ref "U5") (pin "14") (pinfunction "VCC_14") (pintype "bidirectional"))
      (node (ref "U5") (pin "24") (pinfunction "AVCC_24") (pintype "bidirectional"))
      (node (ref "U5") (pin "34") (pinfunction "VCC_34") (pintype "bidirectional"))
      (node (ref "U5") (pin "44") (pinfunction "AVCC_44") (pintype "bidirectional"))
    )
    (net (code "2") (name "BAT") (class "Default")
      (node (ref "C14") (pin "2") (pinfunction "2_2") (pintype "passive"))
      (node (ref "J24") (pin "+") (pinfunction "1_+") (pintype "bidirectional"))
      (node (ref "Q2") (pin "2") (pinfunction "S_2") (pintype "passive"))
      (node (ref "Q3") (pin "3") (pinfunction "D_3") (pintype "passive"))
      (node (ref "R10") (pin "2") (pinfunction "2_2") (pintype "passive"))
      (node (ref "R13") (pin "2") (pinfunction "2_2") (pintype "passive"))
      (node (ref "R22") (pin "2") (pinfunction "2_2") (pintype "passive"))
      (node (ref "U2") (pin "5") (pinfunction "BAT_5") (pintype "bidirectional"))
      (node (ref "U2") (pin "8") (pinfunction "FB_8") (pintype "input"))
    )
    (net (code "3") (name "BEE_3V3") (class "Default")
      (node (ref "C28") (pin "2") (pinfunction "2_2") (pintype "passive"))
      (node (ref "Q1") (pin "3") (pinfunction "D_3") (pintype "passive"))
      (node (ref "SJ8") (pin "1") (pinfunction "1_1") (pintype "passive"))
      (node (ref "XB1") (pin "1") (pinfunction "VCC_1") (pintype "power_in"))
    )
    (net (code "4") (name "BEE_EN") (class "Default")
      (node (ref "R32") (pin "2") (pinfunction "2_2") (pintype "passive"))
      (node (ref "SJ3") (pin "1") (pinfunction "1_1") (pintype "passive"))
      (node (ref "SJ6") (pin "1") (pinfunction "1_1") (pintype "passive"))
      (node (ref "U5") (pin "29") (pinfunction "PB5(PCINT5/OC1A/ADC12/~{OC4B})_29") (pintype "bidirectional"))
    )
    (net (code "5") (name "BEE_RI") (class "Default")
      (node (ref "SJ2") (pin "2") (pinfunction "2_2") (pintype "passive"))
      (node (ref "U5") (pin "1") (pinfunction "PE6(INT.6/AIN0)_1") (pintype "bidirectional"))
    )
    (net (code "6") (name "CH") (class "Default")
      (node (ref "D2") (pin "-") (pinfunction "-_-") (pintype "passive"))
      (node (ref "R7") (pin "1") (pinfunction "1_1") (pintype "passive"))
      (node (ref "U2") (pin "7") (pinfunction "CHRG_7") (pintype "bidirectional"))
    )
    (net (code "7") (name "D+") (class "Default")
      (node (ref "J8") (pin "3") (pinfunction "DP_3") (pintype "bidirectional"))
      (node (ref "R19") (pin "1") (pinfunction "1_1") (pintype "passive"))
    )
    (net (code "8") (name "D-") (class "Default")
      (node (ref "J8") (pin "2") (pinfunction "DM_2") (pintype "bidirectional"))
      (node (ref "R31") (pin "1") (pinfunction "1_1") (pintype "passive"))
    )
    (net (code "9") (name "DIR1") (class "Default")
      (node (ref "J20") (pin "8") (pinfunction "8_8") (pintype "bidirectional"))
      (node (ref "U5") (pin "22") (pinfunction "PD5(XCLK1/~{CTS})_22") (pintype "bidirectional"))
    )
    (net (code "10") (name "DIR2") (class "Default")
      (node (ref "J15") (pin "8") (pinfunction "8_8") (pintype "bidirectional"))
      (node (ref "U5") (pin "12") (pinfunction "PB7(PCINT7/OC0A/OC1C/~{RTS})_12") (pintype "bidirectional"))
    )
    (net (code "11") (name "G1A") (class "Default")
      (node (ref "J2") (pin "1") (pinfunction "1_1") (pintype "bidirectional"))
      (node (ref "JP1") (pin "1") (pinfunction "1_1") (pintype "passive"))
      (node (ref "U5") (pin "36") (pinfunction "PF7(ADC7/TDI)_36") (pintype "bidirectional"))
    )
    (net (code "12") (name "G1B") (class "Default")
      (node (ref "J2") (pin "2") (pinfunction "2_2") (pintype "bidirectional"))
      (node (ref "JP2") (pin "1") (pinfunction "1_1") (pintype "passive"))
      (node (ref "U5") (pin "37") (pinfunction "PF6(ADC6/TDO)_37") (pintype "bidirectional"))
    )
    (net (code "13") (name "G2A") (class "Default")
      (node (ref "J3") (pin "1") (pinfunction "1_1") (pintype "bidirectional"))
      (node (ref "JP3") (pin "1") (pinfunction "1_1") (pintype "passive"))
      (node (ref "U5") (pin "38") (pinfunction "PF5(ADC5/TMS)_38") (pintype "bidirectional"))
    )
    (net (code "14") (name "G2B") (class "Default")
      (node (ref "J3") (pin "2") (pinfunction "2_2") (pintype "bidirectional"))
      (node (ref "JP4") (pin "1") (pinfunction "1_1") (pintype "passive"))
      (node (ref "U5") (pin "39") (pinfunction "PF4(ADC4/TCK)_39") (pintype "bidirectional"))
    )
    (net (code "15") (name "G3A") (class "Default")
      (node (ref "J18") (pin "1") (pinfunction "1_1") (pintype "bidirectional"))
      (node (ref "JP7") (pin "1") (pinfunction "1_1") (pintype "passive"))
      (node (ref "U5") (pin "40") (pinfunction "PF1(ADC1)_40") (pintype "bidirectional"))
    )
    (net (code "16") (name "GND") (class "Default")
      (node (ref "BAT2") (pin "-") (pinfunction "V-_-") (pintype "bidirectional"))
      (node (ref "C1") (pin "1") (pinfunction "1_1") (pintype "passive"))
      (node (ref "C10") (pin "1") (pinfunction "1_1") (pintype "passive"))
      (node (ref "C11") (pin "1") (pinfunction "1_1") (pintype "passive"))
      (node (ref "C12") (pin "2") (pinfunction "2_2") (pintype "passive"))
      (node (ref "C13") (pin "2") (pinfunction "2_2") (pintype "passive"))
      (node (ref "C14") (pin "1") (pinfunction "1_1") (pintype "passive"))
      (node (ref "C16") (pin "-") (pinfunction "-_-") (pintype "passive"))
      (node (ref "C17") (pin "-") (pinfunction "-_-") (pintype "passive"))
      (node (ref "C18") (pin "1") (pinfunction "1_1") (pintype "passive"))
      (node (ref "C19") (pin "-") (pinfunction "-_-") (pintype "passive"))
      (node (ref "C20") (pin "1") (pinfunction "1_1") (pintype "passive"))
      (node (ref "C22") (pin "1") (pinfunction "1_1") (pintype "passive"))
      (node (ref "C23") (pin "1") (pinfunction "1_1") (pintype "passive"))
      (node (ref "C24") (pin "1") (pinfunction "1_1") (pintype "passive"))
      (node (ref "C25") (pin "-") (pinfunction "-_-") (pintype "passive"))
      (node (ref "C26") (pin "-") (pinfunction "-_-") (pintype "passive"))
      (node (ref "C27") (pin "1") (pinfunction "1_1") (pintype "passive"))
      (node (ref "C28") (pin "1") (pinfunction "1_1") (pintype "passive"))
      (node (ref "C30") (pin "1") (pinfunction "1_1") (pintype "passive"))
      (node (ref "C31") (pin "-") (pinfunction "-_-") (pintype "passive"))
      (node (ref "C32") (pin "2") (pinfunction "2_2") (pintype "passive"))
      (node (ref "C33") (pin "1") (pinfunction "1_1") (pintype "passive"))
      (node (ref "C34") (pin "1") (pinfunction "1_1") (pintype "passive"))
      (node (ref "C35") (pin "-") (pinfunction "-_-") (pintype "passive"))
      (node (ref "C36") (pin "1") (pinfunction "1_1") (pintype "passive"))
      (node (ref "C5") (pin "-") (pinfunction "-_-") (pintype "passive"))
      (node (ref "C6") (pin "2") (pinfunction "2_2") (pintype "passive"))
      (node (ref "C7") (pin "1") (pinfunction "1_1") (pintype "passive"))
      (node (ref "C8") (pin "-") (pinfunction "-_-") (pintype "passive"))
      (node (ref "C9") (pin "2") (pinfunction "2_2") (pintype "passive"))
      (node (ref "D1") (pin "-") (pinfunction "-_-") (pintype "passive"))
      (node (ref "D13") (pin "-") (pinfunction "-_-") (pintype "passive"))
      (node (ref "D14") (pin "-") (pinfunction "-_-") (pintype "passive"))
      (node (ref "D15") (pin "-") (pinfunction "-_-") (pintype "passive"))
      (node (ref "D6") (pin "-") (pinfunction "-_-") (pintype "passive"))
      (node (ref "D9") (pin "-") (pinfunction "-_-") (pintype "passive"))
      (node (ref "J1") (pin "6") (pinfunction "VSS_6") (pintype "bidirectional"))
      (node (ref "J1") (pin "G1") (pinfunction "G1_G1") (pintype "bidirectional"))
      (node (ref "J1") (pin "G2") (pinfunction "G2_G2") (pintype "bidirectional"))
      (node (ref "J1") (pin "G3") (pinfunction "G3_G3") (pintype "bidirectional"))
      (node (ref "J1") (pin "G4") (pinfunction "G4_G4") (pintype "bidirectional"))
      (node (ref "J10") (pin "4") (pinfunction "4_4") (pintype "bidirectional"))
      (node (ref "J11") (pin "2") (pinfunction "P$2_2") (pintype "bidirectional"))
      (node (ref "J13") (pin "4") (pinfunction "4_4") (pintype "bidirectional"))
      (node (ref "J14") (pin "2") (pinfunction "P$2_2") (pintype "bidirectional"))
      (node (ref "J17") (pin "2") (pinfunction "2_2") (pintype "bidirectional"))
      (node (ref "J17") (pin "8") (pinfunction "8_8") (pintype "bidirectional"))
      (node (ref "J18") (pin "4") (pinfunction "4_4") (pintype "bidirectional"))
      (node (ref "J2") (pin "4") (pinfunction "4_4") (pintype "bidirectional"))
      (node (ref "J21") (pin "2") (pinfunction "2_2") (pintype "bidirectional"))
      (node (ref "J21") (pin "8") (pinfunction "8_8") (pintype "bidirectional"))
      (node (ref "J24") (pin "-") (pinfunction "2_-") (pintype "bidirectional"))
      (node (ref "J3") (pin "4") (pinfunction "4_4") (pintype "bidirectional"))
      (node (ref "J4") (pin "4") (pinfunction "4_4") (pintype "bidirectional"))
      (node (ref "J5") (pin "1") (pinfunction "1_1") (pintype "bidirectional"))
      (node (ref "J6") (pin "2") (pinfunction "2_2") (pintype "bidirectional"))
      (node (ref "J8") (pin "5") (pinfunction "GND_5") (pintype "bidirectional"))
      (node (ref "J8") (pin "S1") (pinfunction "GND_S1") (pintype "bidirectional"))
      (node (ref "J8") (pin "S2") (pinfunction "GND_S2") (pintype "bidirectional"))
      (node (ref "J8") (pin "S3") (pinfunction "GND_S3") (pintype "bidirectional"))
      (node (ref "J8") (pin "S4") (pinfunction "GND_S4") (pintype "bidirectional"))
      (node (ref "J8") (pin "S5") (pinfunction "GND_S5") (pintype "bidirectional"))
      (node (ref "J8") (pin "S6") (pinfunction "GND_S6") (pintype "bidirectional"))
      (node (ref "JP1") (pin "3") (pinfunction "3_3") (pintype "passive"))
      (node (ref "JP2") (pin "3") (pinfunction "3_3") (pintype "passive"))
      (node (ref "JP3") (pin "3") (pinfunction "3_3") (pintype "passive"))
      (node (ref "JP4") (pin "3") (pinfunction "3_3") (pintype "passive"))
      (node (ref "JP5") (pin "1") (pinfunction "1_1") (pintype "passive"))
      (node (ref "JP7") (pin "3") (pinfunction "3_3") (pintype "passive"))
      (node (ref "Q4") (pin "2") (pinfunction "E_2") (pintype "passive"))
      (node (ref "R17") (pin "2") (pinfunction "2_2") (pintype "passive"))
      (node (ref "R2") (pin "2") (pinfunction "2_2") (pintype "passive"))
      (node (ref "R21") (pin "1") (pinfunction "1_1") (pintype "passive"))
      (node (ref "R24") (pin "2") (pinfunction "2_2") (pintype "passive"))
      (node (ref "R5") (pin "1") (pinfunction "1_1") (pintype "passive"))
      (node (ref "R6") (pin "1") (pinfunction "1_1") (pintype "passive"))
      (node (ref "U$1") (pin "1") (pinfunction "GND_1") (pintype "bidirectional"))
      (node (ref "U1") (pin "4") (pinfunction "GND_4") (pintype "bidirectional"))
      (node (ref "U2") (pin "1") (pinfunction "TEMP_1") (pintype "input"))
      (node (ref "U2") (pin "3") (pinfunction "GND_3") (pintype "power_in"))
      (node (ref "U2") (pin "HEAT") (pinfunction "H_HEAT") (pintype "bidirectional"))
      (node (ref "U3") (pin "15") (pinfunction "PGND_15") (pintype "bidirectional"))
      (node (ref "U3") (pin "16") (pinfunction "PGND_16") (pintype "bidirectional"))
      (node (ref "U3") (pin "5") (pinfunction "FB_5") (pintype "bidirectional"))
      (node (ref "U3") (pin "6") (pinfunction "AGND_6") (pintype "bidirectional"))
      (node (ref "U3") (pin "7") (pinfunction "FSW_7") (pintype "bidirectional"))
      (node (ref "U3") (pin "8") (pinfunction "DEF_8") (pintype "bidirectional"))
      (node (ref "U5") (pin "15") (pinfunction "GND_15") (pintype "bidirectional"))
      (node (ref "U5") (pin "23") (pinfunction "GND_23") (pintype "bidirectional"))
      (node (ref "U5") (pin "35") (pinfunction "GND_35") (pintype "bidirectional"))
      (node (ref "U5") (pin "43") (pinfunction "GND_43") (pintype "bidirectional"))
      (node (ref "U5") (pin "5") (pinfunction "UGND_5") (pintype "bidirectional"))
      (node (ref "U7") (pin "2") (pinfunction "GND_2") (pintype "power_in"))
      (node (ref "XB1") (pin "10") (pinfunction "GND_10") (pintype "power_in"))
      (node (ref "Y1") (pin "2") (pinfunction "2_2") (pintype "passive"))
    )
    (net (code "17") (name "MISO") (class "Default")
      (node (ref "J1") (pin "7") (pinfunction "DO_7") (pintype "bidirectional"))
      (node (ref "J13") (pin "1") (pinfunction "1_1") (pintype "bidirectional"))
      (node (ref "U5") (pin "11") (pinfunction "PB3(PD0/PCINT3/MISO)_11") (pintype "bidirectional"))
    )
    (net (code "18") (name "MOSI") (class "Default")
      (node (ref "J1") (pin "3") (pinfunction "DI_3") (pintype "bidirectional"))
      (node (ref "J13") (pin "5") (pinfunction "5_5") (pintype "bidirectional"))
      (node (ref "U5") (pin "10") (pinfunction "PB2(PDI/PCINT2/MOSI)_10") (pintype "bidirectional"))
    )
    (net (code "19") (name "Net-(BAT2-V+)") (class "Default")
      (node (ref "BAT2") (pin "+") (pinfunction "V+_+") (pintype "bidirectional"))
      (node (ref "D11") (pin "+") (pinfunction "+_+") (pintype "passive"))
    )
    (net (code "20") (name "Net-(C12-Pad1)") (class "Default")
      (node (ref "C12") (pin "1") (pinfunction "1_1") (pintype "passive"))
      (node (ref "R10") (pin "1") (pinfunction "1_1") (pintype "passive"))
      (node (ref "R11") (pin "2") (pinfunction "2_2") (pintype "passive"))
      (node (ref "R12") (pin "2") (pinfunction "2_2") (pintype "passive"))
    )
    (net (code "21") (name "Net-(C15-Pad2)") (class "Default")
      (node (ref "C15") (pin "2") (pinfunction "2_2") (pintype "passive"))
      (node (ref "SJ4") (pin "2") (pinfunction "2_2") (pintype "passive"))
    )
    (net (code "22") (name "Net-(C31-Pad+)") (class "Default")
      (node (ref "C31") (pin "+") (pinfunction "+_+") (pintype "passive"))
      (node (ref "J7") (pin "1") (pinfunction "1_1") (pintype "bidirectional"))
      (node (ref "SW2") (pin "CH1A") (pinfunction "CH1A_CH1A") (pintype "bidirectional"))
      (node (ref "U3") (pin "11") (pinfunction "PVIN_11") (pintype "bidirectional"))
      (node (ref "U3") (pin "12") (pinfunction "PVIN_12") (pintype "bidirectional"))
    )
    (net (code "23") (name "Net-(D1-Pad+)") (class "Default")
      (node (ref "D1") (pin "+") (pinfunction "+_+") (pintype "passive"))
      (node (ref "R1") (pin "1") (pinfunction "1_1") (pintype "passive"))
    )
    (net (code "24") (name "Net-(D2-Pad+)") (class "Default")
      (node (ref "D2") (pin "+") (pinfunction "+_+") (pintype "passive"))
      (node (ref "D7") (pin "+") (pinfunction "+_+") (pintype "passive"))
      (node (ref "R4") (pin "1") (pinfunction "1_1") (pintype "passive"))
    )
    (net (code "25") (name "Net-(D5-Pad+)") (class "Default")
      (node (ref "D5") (pin "+") (pinfunction "+_+") (pintype "passive"))
      (node (ref "J5") (pin "2") (pinfunction "2_2") (pintype "bidirectional"))
    )
    (net (code "26") (name "Net-(D6-Pad+)") (class "Default")
      (node (ref "D6") (pin "+") (pinfunction "+_+") (pintype "passive"))
      (node (ref "R15") (pin "2") (pinfunction "2_2") (pintype "passive"))
    )
    (net (code "27") (name "Net-(D9-Pad+)") (class "Default")
      (node (ref "D9") (pin "+") (pinfunction "+_+") (pintype "passive"))
      (node (ref "R28") (pin "1") (pinfunction "1_1") (pintype "passive"))
    )
    (net (code "28") (name "Net-(D10-+)") (class "Default")
      (node (ref "D10") (pin "A") (pinfunction "+_A") (pintype "passive"))
      (node (ref "Q4") (pin "3") (pinfunction "C_3") (pintype "passive"))
      (node (ref "SW1") (pin "3") (pinfunction "V-_3") (pintype "bidirectional"))
    )
    (net (code "29") (name "Net-(D13-Pad+)") (class "Default")
      (node (ref "D13") (pin "+") (pinfunction "+_+") (pintype "passive"))
      (node (ref "R32") (pin "1") (pinfunction "1_1") (pintype "passive"))
    )
    (net (code "30") (name "Net-(D14-Pad+)") (class "Default")
      (node (ref "D14") (pin "+") (pinfunction "+_+") (pintype "passive"))
      (node (ref "R33") (pin "2") (pinfunction "2_2") (pintype "passive"))
    )
    (net (code "31") (name "Net-(D15-Pad+)") (class "Default")
      (node (ref "D15") (pin "+") (pinfunction "+_+") (pintype "passive"))
      (node (ref "R9") (pin "2") (pinfunction "2_2") (pintype "passive"))
    )
    (net (code "32") (name "Net-(J8-VCC)") (class "Default")
      (node (ref "F2") (pin "1") (pinfunction "1_1") (pintype "bidirectional"))
      (node (ref "J8") (pin "1") (pinfunction "VCC_1") (pintype "bidirectional"))
    )
    (net (code "33") (name "Net-(J12-Pad1)") (class "Default")
      (node (ref "J12") (pin "1") (pinfunction "1_1") (pintype "bidirectional"))
      (node (ref "J15") (pin "2") (pinfunction "2_2") (pintype "bidirectional"))
    )
    (net (code "34") (name "Net-(J12-Pad2)") (class "Default")
      (node (ref "J12") (pin "2") (pinfunction "2_2") (pintype "bidirectional"))
      (node (ref "J15") (pin "3") (pinfunction "3_3") (pintype "bidirectional"))
    )
    (net (code "35") (name "Net-(J12-Pad3)") (class "Default")
      (node (ref "J12") (pin "3") (pinfunction "3_3") (pintype "bidirectional"))
      (node (ref "J15") (pin "4") (pinfunction "4_4") (pintype "bidirectional"))
    )
    (net (code "36") (name "Net-(J15-Pad5)") (class "Default")
      (node (ref "J15") (pin "5") (pinfunction "5_5") (pintype "bidirectional"))
      (node (ref "J15") (pin "6") (pinfunction "6_6") (pintype "bidirectional"))
    )
    (net (code "37") (name "Net-(J16-Pad1)") (class "Default")
      (node (ref "J16") (pin "1") (pinfunction "1_1") (pintype "bidirectional"))
      (node (ref "J20") (pin "2") (pinfunction "2_2") (pintype "bidirectional"))
    )
    (net (code "38") (name "Net-(J16-Pad2)") (class "Default")
      (node (ref "J16") (pin "2") (pinfunction "2_2") (pintype "bidirectional"))
      (node (ref "J20") (pin "3") (pinfunction "3_3") (pintype "bidirectional"))
    )
    (net (code "39") (name "Net-(J16-Pad3)") (class "Default")
      (node (ref "J16") (pin "3") (pinfunction "3_3") (pintype "bidirectional"))
      (node (ref "J20") (pin "4") (pinfunction "4_4") (pintype "bidirectional"))
    )
    (net (code "40") (name "Net-(J19-P$1)") (class "Default")
      (node (ref "J19") (pin "1") (pinfunction "P$1_1") (pintype "bidirectional"))
      (node (ref "SW1") (pin "4") (pinfunction "NO_4") (pintype "bidirectional"))
    )
    (net (code "41") (name "Net-(J19-P$2)") (class "Default")
      (node (ref "J19") (pin "2") (pinfunction "P$2_2") (pintype "bidirectional"))
      (node (ref "SW1") (pin "1") (pinfunction "COM_1") (pintype "bidirectional"))
    )
    (net (code "42") (name "Net-(J19-P$3)") (class "Default")
      (node (ref "J19") (pin "3") (pinfunction "P$3_3") (pintype "bidirectional"))
      (node (ref "SW1") (pin "5") (pinfunction "NC_5") (pintype "bidirectional"))
    )
    (net (code "43") (name "Net-(J20-Pad5)") (class "Default")
      (node (ref "J20") (pin "5") (pinfunction "5_5") (pintype "bidirectional"))
      (node (ref "J20") (pin "6") (pinfunction "6_6") (pintype "bidirectional"))
    )
    (net (code "44") (name "Net-(J22-P$1)") (class "Default")
      (node (ref "J21") (pin "3") (pinfunction "3_3") (pintype "bidirectional"))
      (node (ref "J22") (pin "1") (pinfunction "P$1_1") (pintype "bidirectional"))
    )
    (net (code "45") (name "Net-(J22-P$2)") (class "Default")
      (node (ref "J21") (pin "4") (pinfunction "4_4") (pintype "bidirectional"))
      (node (ref "J22") (pin "2") (pinfunction "P$2_2") (pintype "bidirectional"))
    )
    (net (code "46") (name "Net-(J22-P$3)") (class "Default")
      (node (ref "J21") (pin "5") (pinfunction "5_5") (pintype "bidirectional"))
      (node (ref "J22") (pin "3") (pinfunction "P$3_3") (pintype "bidirectional"))
    )
    (net (code "47") (name "Net-(J22-P$4)") (class "Default")
      (node (ref "J21") (pin "6") (pinfunction "6_6") (pintype "bidirectional"))
      (node (ref "J22") (pin "4") (pinfunction "P$4_4") (pintype "bidirectional"))
    )
    (net (code "48") (name "Net-(J23-P$1)") (class "Default")
      (node (ref "J17") (pin "3") (pinfunction "3_3") (pintype "bidirectional"))
      (node (ref "J23") (pin "1") (pinfunction "P$1_1") (pintype "bidirectional"))
    )
    (net (code "49") (name "Net-(J23-P$2)") (class "Default")
      (node (ref "J17") (pin "4") (pinfunction "4_4") (pintype "bidirectional"))
      (node (ref "J23") (pin "2") (pinfunction "P$2_2") (pintype "bidirectional"))
    )
    (net (code "50") (name "Net-(J23-P$3)") (class "Default")
      (node (ref "J17") (pin "5") (pinfunction "5_5") (pintype "bidirectional"))
      (node (ref "J23") (pin "3") (pinfunction "P$3_3") (pintype "bidirectional"))
    )
    (net (code "51") (name "Net-(J23-P$4)") (class "Default")
      (node (ref "J17") (pin "6") (pinfunction "6_6") (pintype "bidirectional"))
      (node (ref "J23") (pin "4") (pinfunction "P$4_4") (pintype "bidirectional"))
    )
    (net (code "52") (name "Net-(K1-Pad2)") (class "Default")
      (node (ref "K1") (pin "2") (pinfunction "2_2") (pintype "bidirectional"))
      (node (ref "R4") (pin "2") (pinfunction "2_2") (pintype "passive"))
    )
    (net (code "53") (name "Net-(L1-Pad1)") (class "Default")
      (node (ref "L1") (pin "1") (pinfunction "1_1") (pintype "passive"))
      (node (ref "U3") (pin "1") (pinfunction "SW_1") (pintype "bidirectional"))
      (node (ref "U3") (pin "2") (pinfunction "SW_2") (pintype "bidirectional"))
      (node (ref "U3") (pin "3") (pinfunction "SW_3") (pintype "bidirectional"))
    )
    (net (code "54") (name "Net-(Q1-G)") (class "Default")
      (node (ref "Q1") (pin "1") (pinfunction "G_1") (pintype "passive"))
      (node (ref "R3") (pin "2") (pinfunction "2_2") (pintype "passive"))
      (node (ref "SJ3") (pin "2") (pinfunction "2_2") (pintype "passive"))
    )
    (net (code "55") (name "Net-(Q2-G)") (class "Default")
      (node (ref "Q2") (pin "1") (pinfunction "G_1") (pintype "passive"))
      (node (ref "R22") (pin "1") (pinfunction "1_1") (pintype "passive"))
      (node (ref "SJ5") (pin "2") (pinfunction "2_2") (pintype "passive"))
    )
    (net (code "56") (name "Net-(Q3-S)") (class "Default")
      (node (ref "C1") (pin "2") (pinfunction "2_2") (pintype "passive"))
      (node (ref "D3") (pin "-") (pinfunction "-_-") (pintype "passive"))
      (node (ref "J7") (pin "2") (pinfunction "2_2") (pintype "bidirectional"))
      (node (ref "Q3") (pin "2") (pinfunction "S_2") (pintype "passive"))
      (node (ref "SW2") (pin "COM1") (pinfunction "COM1_COM1") (pintype "bidirectional"))
    )
    (net (code "57") (name "Net-(Q4-B)") (class "Default")
      (node (ref "Q4") (pin "1") (pinfunction "B_1") (pintype "passive"))
      (node (ref "R16") (pin "2") (pinfunction "2_2") (pintype "passive"))
    )
    (net (code "58") (name "Net-(Q5-G)") (class "Default")
      (node (ref "Q5") (pin "1") (pinfunction "G_1") (pintype "passive"))
      (node (ref "R8") (pin "1") (pinfunction "1_1") (pintype "passive"))
      (node (ref "SJ1") (pin "2") (pinfunction "2_2") (pintype "passive"))
    )
    (net (code "59") (name "Net-(Q8-D)") (class "Default")
      (node (ref "C30") (pin "2") (pinfunction "2_2") (pintype "passive"))
      (node (ref "Q8") (pin "3") (pinfunction "D_3") (pintype "passive"))
      (node (ref "U$1") (pin "16") (pinfunction "VCC_16") (pintype "bidirectional"))
    )
    (net (code "60") (name "Net-(Q8-G)") (class "Default")
      (node (ref "Q8") (pin "1") (pinfunction "G_1") (pintype "passive"))
      (node (ref "R17") (pin "1") (pinfunction "1_1") (pintype "passive"))
      (node (ref "SJ8") (pin "2") (pinfunction "2_2") (pintype "passive"))
    )
    (net (code "61") (name "Net-(R11-Pad1)") (class "Default")
      (node (ref "R11") (pin "1") (pinfunction "1_1") (pintype "passive"))
      (node (ref "R7") (pin "2") (pinfunction "2_2") (pintype "passive"))
    )
    (net (code "62") (name "Net-(R14-Pad1)") (class "Default")
      (node (ref "R14") (pin "1") (pinfunction "1_1") (pintype "passive"))
      (node (ref "R6") (pin "2") (pinfunction "2_2") (pintype "passive"))
    )
    (net (code "63") (name "Net-(U1-X1)") (class "Default")
      (node (ref "U1") (pin "1") (pinfunction "X1_1") (pintype "bidirectional"))
      (node (ref "X1") (pin "1") (pinfunction "1_1") (pintype "passive"))
    )
    (net (code "64") (name "Net-(U1-X2)") (class "Default")
      (node (ref "U1") (pin "2") (pinfunction "X2_2") (pintype "bidirectional"))
      (node (ref "X1") (pin "2") (pinfunction "2_2") (pintype "passive"))
    )
    (net (code "65") (name "Net-(U2-ISET)") (class "Default")
      (node (ref "R2") (pin "1") (pinfunction "1_1") (pintype "passive"))
      (node (ref "U2") (pin "2") (pinfunction "ISET_2") (pintype "bidirectional"))
    )
    (net (code "66") (name "Net-(U3-AVIN)") (class "Default")
      (node (ref "C32") (pin "1") (pinfunction "1_1") (pintype "passive"))
      (node (ref "U3") (pin "10") (pinfunction "AVIN_10") (pintype "bidirectional"))
      (node (ref "U3") (pin "13") (pinfunction "EN_13") (pintype "bidirectional"))
    )
    (net (code "67") (name "Net-(U3-PG)") (class "Default")
      (node (ref "R23") (pin "1") (pinfunction "1_1") (pintype "passive"))
      (node (ref "U3") (pin "4") (pinfunction "PG_4") (pintype "bidirectional"))
    )
    (net (code "68") (name "Net-(U3-SS{slash}TR)") (class "Default")
      (node (ref "C33") (pin "2") (pinfunction "2_2") (pintype "passive"))
      (node (ref "C34") (pin "2") (pinfunction "2_2") (pintype "passive"))
      (node (ref "C36") (pin "2") (pinfunction "2_2") (pintype "passive"))
      (node (ref "U3") (pin "9") (pinfunction "SS/TR_9") (pintype "bidirectional"))
    )
    (net (code "69") (name "Net-(U5-AREF)") (class "Default")
      (node (ref "C6") (pin "1") (pinfunction "1_1") (pintype "passive"))
      (node (ref "U5") (pin "42") (pinfunction "AREF_42") (pintype "bidirectional"))
    )
    (net (code "70") (name "Net-(U5-D+)") (class "Default")
      (node (ref "R19") (pin "2") (pinfunction "2_2") (pintype "passive"))
      (node (ref "U5") (pin "4") (pinfunction "D+_4") (pintype "bidirectional"))
    )
    (net (code "71") (name "Net-(U5-D-)") (class "Default")
      (node (ref "R31") (pin "2") (pinfunction "2_2") (pintype "passive"))
      (node (ref "U5") (pin "3") (pinfunction "D-_3") (pintype "bidirectional"))
    )
    (net (code "72") (name "Net-(U5-PE2(~{HWB}))") (class "Default")
      (node (ref "R24") (pin "1") (pinfunction "1_1") (pintype "passive"))
      (node (ref "U5") (pin "33") (pinfunction "PE2(~{HWB})_33") (pintype "bidirectional"))
    )
    (net (code "73") (name "Net-(U5-UCAP)") (class "Default")
      (node (ref "C9") (pin "1") (pinfunction "1_1") (pintype "passive"))
      (node (ref "U5") (pin "6") (pinfunction "UCAP_6") (pintype "bidirectional"))
    )
    (net (code "74") (name "Net-(U5-XTAL1)") (class "Default")
      (node (ref "U5") (pin "17") (pinfunction "XTAL1_17") (pintype "bidirectional"))
      (node (ref "Y1") (pin "1") (pinfunction "1_1") (pintype "passive"))
    )
    (net (code "75") (name "Net-(U5-XTAL2)") (class "Default")
      (node (ref "U5") (pin "16") (pinfunction "XTAL2_16") (pintype "bidirectional"))
      (node (ref "Y1") (pin "3") (pinfunction "3_3") (pintype "passive"))
    )
    (net (code "76") (name "Net-(U7-FB)") (class "Default")
      (node (ref "C21") (pin "1") (pinfunction "1_1") (pintype "passive"))
      (node (ref "R20") (pin "1") (pinfunction "1_1") (pintype "passive"))
      (node (ref "R21") (pin "2") (pinfunction "2_2") (pintype "passive"))
      (node (ref "U7") (pin "3") (pinfunction "FB_3") (pintype "input"))
    )
    (net (code "77") (name "Net-(U7-LX)") (class "Default")
      (node (ref "D8") (pin "+") (pinfunction "+_+") (pintype "passive"))
      (node (ref "L3") (pin "2") (pinfunction "2_2") (pintype "passive"))
      (node (ref "U7") (pin "1") (pinfunction "LX_1") (pintype "output"))
    )
    (net (code "78") (name "Net-(U7-SS)") (class "Default")
      (node (ref "C20") (pin "2") (pinfunction "2_2") (pintype "passive"))
      (node (ref "U7") (pin "5") (pinfunction "SS_5") (pintype "input"))
    )
    (net (code "79") (name "Net-(U7-~{SHDN})") (class "Default")
      (node (ref "R18") (pin "2") (pinfunction "2_2") (pintype "passive"))
      (node (ref "U7") (pin "4") (pinfunction "~{SHDN}_4") (pintype "input"))
    )
    (net (code "80") (name "Net-(XB1-AD0{slash}DIO0)") (class "Default")
      (node (ref "SJ2") (pin "3") (pinfunction "3_3") (pintype "passive"))
      (node (ref "XB1") (pin "20") (pinfunction "AD0/DIO0_20") (pintype "bidirectional"))
    )
    (net (code "81") (name "Net-(XB1-AD3{slash}DIO3)") (class "Default")
      (node (ref "SJ4") (pin "1") (pinfunction "1_1") (pintype "passive"))
      (node (ref "XB1") (pin "17") (pinfunction "AD3/DIO3_17") (pintype "bidirectional"))
    )
    (net (code "82") (name "Net-(XB1-ASSOC{slash}DIO5)") (class "Default")
      (node (ref "SJ2") (pin "1") (pinfunction "1_1") (pintype "passive"))
      (node (ref "XB1") (pin "15") (pinfunction "ASSOC/DIO5_15") (pintype "bidirectional"))
    )
    (net (code "83") (name "Net-(XB1-~{CTS}{slash}DIO7)") (class "Default")
      (node (ref "R1") (pin "2") (pinfunction "2_2") (pintype "passive"))
      (node (ref "XB1") (pin "12") (pinfunction "~{CTS}/DIO7_12") (pintype "bidirectional"))
    )
    (net (code "84") (name "Net-(XB1-~{DTR}{slash}SLEEP_RQ{slash}DIO8)") (class "Default")
      (node (ref "SJ6") (pin "2") (pinfunction "2_2") (pintype "passive"))
      (node (ref "XB1") (pin "9") (pinfunction "~{DTR}/SLEEP_RQ/DIO8_9") (pintype "bidirectional"))
    )
    (net (code "85") (name "OK") (class "Default")
      (node (ref "D7") (pin "-") (pinfunction "-_-") (pintype "passive"))
      (node (ref "R12") (pin "1") (pinfunction "1_1") (pintype "passive"))
      (node (ref "U2") (pin "6") (pinfunction "DONE_6") (pintype "bidirectional"))
    )
    (net (code "86") (name "PAP1_3V3") (class "Default")
      (node (ref "C27") (pin "2") (pinfunction "2_2") (pintype "passive"))
      (node (ref "J16") (pin "4") (pinfunction "4_4") (pintype "bidirectional"))
      (node (ref "J16") (pin "5") (pinfunction "5_5") (pintype "bidirectional"))
      (node (ref "J16") (pin "6") (pinfunction "6_6") (pintype "bidirectional"))
    )
    (net (code "87") (name "PAP2_3V3") (class "Default")
      (node (ref "C11") (pin "2") (pinfunction "2_2") (pintype "passive"))
      (node (ref "J12") (pin "4") (pinfunction "4_4") (pintype "bidirectional"))
      (node (ref "J12") (pin "5") (pinfunction "5_5") (pintype "bidirectional"))
      (node (ref "J12") (pin "6") (pinfunction "6_6") (pintype "bidirectional"))
    )
    (net (code "88") (name "RELAIS") (class "Default")
      (node (ref "R15") (pin "1") (pinfunction "1_1") (pintype "passive"))
      (node (ref "R16") (pin "1") (pinfunction "1_1") (pintype "passive"))
      (node (ref "U5") (pin "27") (pinfunction "PD7(T0/OC4D/ADC10)_27") (pintype "bidirectional"))
    )
    (net (code "89") (name "RESET") (class "Default")
      (node (ref "C15") (pin "1") (pinfunction "1_1") (pintype "passive"))
      (node (ref "J13") (pin "3") (pinfunction "3_3") (pintype "bidirectional"))
      (node (ref "R30") (pin "1") (pinfunction "1_1") (pintype "passive"))
      (node (ref "U5") (pin "13") (pinfunction "~{RESET}_13") (pintype "bidirectional"))
    )
    (net (code "90") (name "RTC_3V3") (class "Default")
      (node (ref "C10") (pin "2") (pinfunction "2_2") (pintype "passive"))
      (node (ref "C7") (pin "2") (pinfunction "2_2") (pintype "passive"))
      (node (ref "D11") (pin "-") (pinfunction "-_-") (pintype "passive"))
      (node (ref "D12") (pin "-") (pinfunction "-_-") (pintype "passive"))
      (node (ref "U1") (pin "8") (pinfunction "VCC_8") (pintype "bidirectional"))
    )
    (net (code "91") (name "RX") (class "Default")
      (node (ref "U$1") (pin "8") (pinfunction "TXD_8") (pintype "bidirectional"))
      (node (ref "U5") (pin "21") (pinfunction "PD3(TXD1/INT3)_21") (pintype "bidirectional"))
      (node (ref "XB1") (pin "2") (pinfunction "DOUT_2") (pintype "output"))
    )
    (net (code "92") (name "S1") (class "Default")
      (node (ref "J11") (pin "3") (pinfunction "P$3_3") (pintype "bidirectional"))
      (node (ref "U5") (pin "26") (pinfunction "PD6(T1/ADC9/~{OC4D})_26") (pintype "bidirectional"))
    )
    (net (code "93") (name "S2") (class "Default")
      (node (ref "J14") (pin "3") (pinfunction "P$3_3") (pintype "bidirectional"))
      (node (ref "U5") (pin "25") (pinfunction "PD4(ICP1/ADC8)_25") (pintype "bidirectional"))
    )
    (net (code "94") (name "SCK") (class "Default")
      (node (ref "J1") (pin "5") (pinfunction "SCLK_5") (pintype "bidirectional"))
      (node (ref "J13") (pin "2") (pinfunction "2_2") (pintype "bidirectional"))
      (node (ref "U5") (pin "9") (pinfunction "PB1(PCINT1/SCLK)_9") (pintype "bidirectional"))
    )
    (net (code "95") (name "SCL") (class "Default")
      (node (ref "J10") (pin "1") (pinfunction "1_1") (pintype "bidirectional"))
      (node (ref "J4") (pin "1") (pinfunction "1_1") (pintype "bidirectional"))
      (node (ref "JP5") (pin "4") (pinfunction "4_4") (pintype "passive"))
      (node (ref "R26") (pin "2") (pinfunction "2_2") (pintype "passive"))
      (node (ref "U1") (pin "6") (pinfunction "SCL_6") (pintype "bidirectional"))
      (node (ref "U5") (pin "18") (pinfunction "PD0(OC0B/SCL/INT0)_18") (pintype "bidirectional"))
    )
    (net (code "96") (name "SDA") (class "Default")
      (node (ref "J10") (pin "2") (pinfunction "2_2") (pintype "bidirectional"))
      (node (ref "J4") (pin "2") (pinfunction "2_2") (pintype "bidirectional"))
      (node (ref "JP5") (pin "3") (pinfunction "3_3") (pintype "passive"))
      (node (ref "R27") (pin "2") (pinfunction "2_2") (pintype "passive"))
      (node (ref "U1") (pin "5") (pinfunction "SDA_5") (pintype "bidirectional"))
      (node (ref "U5") (pin "19") (pinfunction "PD1(SDA/INT1)_19") (pintype "bidirectional"))
    )
    (net (code "97") (name "SD_3V3") (class "Default")
      (node (ref "C18") (pin "2") (pinfunction "2_2") (pintype "passive"))
      (node (ref "J1") (pin "4") (pinfunction "VDD_4") (pintype "bidirectional"))
      (node (ref "Q5") (pin "3") (pinfunction "D_3") (pintype "passive"))
    )
    (net (code "98") (name "SD_EN") (class "Default")
      (node (ref "R33") (pin "1") (pinfunction "1_1") (pintype "passive"))
      (node (ref "SJ1") (pin "1") (pinfunction "1_1") (pintype "passive"))
      (node (ref "U5") (pin "30") (pinfunction "PB6(PCINT6/OC1B/OC4B/ADC13)_30") (pintype "bidirectional"))
    )
    (net (code "99") (name "SERVO_EN") (class "Default")
      (node (ref "R9") (pin "1") (pinfunction "1_1") (pintype "passive"))
      (node (ref "SJ5") (pin "1") (pinfunction "1_1") (pintype "passive"))
      (node (ref "U5") (pin "28") (pinfunction "PB4(PCINT4/ADC11)_28") (pintype "bidirectional"))
    )
    (net (code "100") (name "SS") (class "Default")
      (node (ref "J1") (pin "2") (pinfunction "CS_2") (pintype "bidirectional"))
      (node (ref "U5") (pin "8") (pinfunction "PB0(SS/PCINT0)_8") (pintype "bidirectional"))
    )
    (net (code "101") (name "STEP1") (class "Default")
      (node (ref "J20") (pin "7") (pinfunction "7_7") (pintype "bidirectional"))
      (node (ref "U5") (pin "32") (pinfunction "PC7(ICP3/CLK0/OC4A)_32") (pintype "bidirectional"))
    )
    (net (code "102") (name "STEP2") (class "Default")
      (node (ref "J15") (pin "7") (pinfunction "7_7") (pintype "bidirectional"))
      (node (ref "U5") (pin "31") (pinfunction "PC6(OC3A/~{OC4A})_31") (pintype "bidirectional"))
    )
    (net (code "103") (name "TX") (class "Default")
      (node (ref "U$1") (pin "7") (pinfunction "RXD_7") (pintype "bidirectional"))
      (node (ref "U5") (pin "20") (pinfunction "PD2(RXD1/INT2)_20") (pintype "bidirectional"))
      (node (ref "XB1") (pin "3") (pinfunction "DIN/~{CONFIG}_3") (pintype "input"))
    )
    (net (code "104") (name "USB_TF") (class "Default")
      (node (ref "SW2") (pin "COM2") (pinfunction "COM2_COM2") (pintype "bidirectional"))
      (node (ref "U5") (pin "2") (pinfunction "UVCC_2") (pintype "bidirectional"))
      (node (ref "U5") (pin "7") (pinfunction "VBUS_7") (pintype "bidirectional"))
    )
    (net (code "105") (name "VEXT") (class "Default")
      (node (ref "C16") (pin "+") (pinfunction "+_+") (pintype "passive"))
      (node (ref "C17") (pin "+") (pinfunction "+_+") (pintype "passive"))
      (node (ref "J17") (pin "1") (pinfunction "1_1") (pintype "bidirectional"))
      (node (ref "J21") (pin "1") (pinfunction "1_1") (pintype "bidirectional"))
      (node (ref "J6") (pin "1") (pinfunction "1_1") (pintype "bidirectional"))
    )
    (net (code "106") (name "VIN") (class "Default")
      (node (ref "C5") (pin "+") (pinfunction "+_+") (pintype "passive"))
      (node (ref "D4") (pin "-") (pinfunction "-_-") (pintype "passive"))
      (node (ref "D5") (pin "-") (pinfunction "-_-") (pintype "passive"))
      (node (ref "K1") (pin "1") (pinfunction "1_1") (pintype "bidirectional"))
      (node (ref "U2") (pin "4") (pinfunction "VIN_4") (pintype "input"))
    )
    (net (code "107") (name "VUSB") (class "Default")
      (node (ref "C8") (pin "+") (pinfunction "+_+") (pintype "passive"))
      (node (ref "D3") (pin "+") (pinfunction "+_+") (pintype "passive"))
      (node (ref "D4") (pin "+") (pinfunction "+_+") (pintype "passive"))
      (node (ref "F2") (pin "2") (pinfunction "2_2") (pintype "bidirectional"))
      (node (ref "Q3") (pin "1") (pinfunction "G_1") (pintype "passive"))
      (node (ref "R5") (pin "2") (pinfunction "2_2") (pintype "passive"))
      (node (ref "SW2") (pin "CH2A") (pinfunction "CH2A_CH2A") (pintype "bidirectional"))
    )
    (net (code "108") (name "V_BAT") (class "Default")
      (node (ref "C13") (pin "1") (pinfunction "1_1") (pintype "passive"))
      (node (ref "R13") (pin "1") (pinfunction "1_1") (pintype "passive"))
      (node (ref "R14") (pin "2") (pinfunction "2_2") (pintype "passive"))
      (node (ref "U5") (pin "41") (pinfunction "PF0(ADC0)_41") (pintype "bidirectional"))
    )
    (net (code "109") (name "V_BOOST") (class "Default")
      (node (ref "C19") (pin "+") (pinfunction "+_+") (pintype "passive"))
      (node (ref "L3") (pin "1") (pinfunction "1_1") (pintype "passive"))
      (node (ref "Q2") (pin "3") (pinfunction "D_3") (pintype "passive"))
      (node (ref "R18") (pin "1") (pinfunction "1_1") (pintype "passive"))
      (node (ref "U7") (pin "6") (pinfunction "IN_6") (pintype "input"))
    )
    (net (code "110") (name "V_SERVO") (class "Default")
      (node (ref "C21") (pin "2") (pinfunction "2_2") (pintype "passive"))
      (node (ref "C22") (pin "2") (pinfunction "2_2") (pintype "passive"))
      (node (ref "C23") (pin "2") (pinfunction "2_2") (pintype "passive"))
      (node (ref "C24") (pin "2") (pinfunction "2_2") (pintype "passive"))
      (node (ref "C25") (pin "+") (pinfunction "+_+") (pintype "passive"))
      (node (ref "C26") (pin "+") (pinfunction "+_+") (pintype "passive"))
      (node (ref "D8") (pin "-") (pinfunction "-_-") (pintype "passive"))
      (node (ref "J11") (pin "1") (pinfunction "P$1_1") (pintype "bidirectional"))
      (node (ref "J14") (pin "1") (pinfunction "P$1_1") (pintype "bidirectional"))
      (node (ref "R20") (pin "2") (pinfunction "2_2") (pintype "passive"))
    )
    (net (code "111") (name "unconnected-(J1-CDN-Pad9)") (class "Default")
      (node (ref "J1") (pin "9") (pinfunction "CDN_9") (pintype "bidirectional"))
    )
    (net (code "112") (name "unconnected-(J1-DATA1-Pad8)") (class "Default")
      (node (ref "J1") (pin "8") (pinfunction "DATA1_8") (pintype "bidirectional"))
    )
    (net (code "113") (name "unconnected-(J1-DATA2-Pad1)") (class "Default")
      (node (ref "J1") (pin "1") (pinfunction "DATA2_1") (pintype "bidirectional"))
    )
    (net (code "114") (name "unconnected-(J8-ID-Pad4)") (class "Default")
      (node (ref "J8") (pin "4") (pinfunction "ID_4") (pintype "bidirectional"))
    )
    (net (code "115") (name "unconnected-(J15-Pad1)") (class "Default")
      (node (ref "J15") (pin "1") (pinfunction "1_1") (pintype "bidirectional"))
    )
    (net (code "116") (name "unconnected-(J18-Pad2)") (class "Default")
      (node (ref "J18") (pin "2") (pinfunction "2_2") (pintype "bidirectional"))
    )
    (net (code "117") (name "unconnected-(J20-Pad1)") (class "Default")
      (node (ref "J20") (pin "1") (pinfunction "1_1") (pintype "bidirectional"))
    )
    (net (code "118") (name "unconnected-(J24-Pad3)") (class "Default")
      (node (ref "J24") (pin "3") (pinfunction "3_3") (pintype "bidirectional"))
    )
    (net (code "119") (name "unconnected-(J24-Pad4)") (class "Default")
      (node (ref "J24") (pin "4") (pinfunction "4_4") (pintype "bidirectional"))
    )
    (net (code "120") (name "unconnected-(K1-PadS1)") (class "Default")
      (node (ref "K1") (pin "S1") (pinfunction "S1_S1") (pintype "bidirectional"))
    )
    (net (code "121") (name "unconnected-(K1-PadS2)") (class "Default")
      (node (ref "K1") (pin "S2") (pinfunction "S2_S2") (pintype "bidirectional"))
    )
    (net (code "122") (name "unconnected-(SW2-PadCH1B)") (class "Default")
      (node (ref "SW2") (pin "CH1B") (pinfunction "CH1B_CH1B") (pintype "bidirectional"))
    )
    (net (code "123") (name "unconnected-(SW2-PadCH2B)") (class "Default")
      (node (ref "SW2") (pin "CH2B") (pinfunction "CH2B_CH2B") (pintype "bidirectional"))
    )
    (net (code "124") (name "unconnected-(U$1-ADC-Pad10)") (class "Default")
      (node (ref "U$1") (pin "10") (pinfunction "ADC_10") (pintype "bidirectional"))
    )
    (net (code "125") (name "unconnected-(U$1-GPIO0-Pad4)") (class "Default")
      (node (ref "U$1") (pin "4") (pinfunction "GPIO0_4") (pintype "bidirectional"))
    )
    (net (code "126") (name "unconnected-(U$1-GPIO2-Pad3)") (class "Default")
      (node (ref "U$1") (pin "3") (pinfunction "GPIO2_3") (pintype "bidirectional"))
    )
    (net (code "127") (name "unconnected-(U$1-GPIO4-Pad6)") (class "Default")
      (node (ref "U$1") (pin "6") (pinfunction "GPIO4_6") (pintype "bidirectional"))
    )
    (net (code "128") (name "unconnected-(U$1-GPIO5-Pad5)") (class "Default")
      (node (ref "U$1") (pin "5") (pinfunction "GPIO5_5") (pintype "bidirectional"))
    )
    (net (code "129") (name "unconnected-(U$1-GPIO12-Pad14)") (class "Default")
      (node (ref "U$1") (pin "14") (pinfunction "GPIO12_14") (pintype "bidirectional"))
    )
    (net (code "130") (name "unconnected-(U$1-GPIO13-Pad15)") (class "Default")
      (node (ref "U$1") (pin "15") (pinfunction "GPIO13_15") (pintype "bidirectional"))
    )
    (net (code "131") (name "unconnected-(U$1-GPIO14-Pad13)") (class "Default")
      (node (ref "U$1") (pin "13") (pinfunction "GPIO14_13") (pintype "bidirectional"))
    )
    (net (code "132") (name "unconnected-(U$1-GPIO15-Pad2)") (class "Default")
      (node (ref "U$1") (pin "2") (pinfunction "GPIO15_2") (pintype "bidirectional"))
    )
    (net (code "133") (name "unconnected-(U$1-GPIO16-Pad12)") (class "Default")
      (node (ref "U$1") (pin "12") (pinfunction "GPIO16_12") (pintype "bidirectional"))
    )
    (net (code "134") (name "unconnected-(U$1-REST-Pad9)") (class "Default")
      (node (ref "U$1") (pin "9") (pinfunction "REST_9") (pintype "bidirectional"))
    )
    (net (code "135") (name "unconnected-(U1-~{INTA}-Pad3)") (class "Default")
      (node (ref "U1") (pin "3") (pinfunction "~{INTA}_3") (pintype "bidirectional"))
    )
    (net (code "136") (name "unconnected-(U1-~{INTB}-Pad7)") (class "Default")
      (node (ref "U1") (pin "7") (pinfunction "~{INTB}_7") (pintype "bidirectional"))
    )
    (net (code "137") (name "unconnected-(XB1-AD1{slash}DIO1-Pad19)") (class "Default")
      (node (ref "XB1") (pin "19") (pinfunction "AD1/DIO1_19") (pintype "bidirectional"))
    )
    (net (code "138") (name "unconnected-(XB1-AD2{slash}DIO2-Pad18)") (class "Default")
      (node (ref "XB1") (pin "18") (pinfunction "AD2/DIO2_18") (pintype "bidirectional"))
    )
    (net (code "139") (name "unconnected-(XB1-DIO4-Pad11)") (class "Default")
      (node (ref "XB1") (pin "11") (pinfunction "DIO4_11") (pintype "bidirectional"))
    )
    (net (code "140") (name "unconnected-(XB1-DIO12-Pad4)") (class "Default")
      (node (ref "XB1") (pin "4") (pinfunction "DIO12_4") (pintype "bidirectional"))
    )
    (net (code "141") (name "unconnected-(XB1-ON{slash}~{SLEEP}-Pad13)") (class "Default")
      (node (ref "XB1") (pin "13") (pinfunction "ON/~{SLEEP}_13") (pintype "output"))
    )
    (net (code "142") (name "unconnected-(XB1-RSSI{slash}PWM{slash}DIO10-Pad6)") (class "Default")
      (node (ref "XB1") (pin "6") (pinfunction "RSSI/PWM/DIO10_6") (pintype "output"))
    )
    (net (code "143") (name "unconnected-(XB1-VREF-Pad14)") (class "Default")
      (node (ref "XB1") (pin "14") (pinfunction "VREF_14") (pintype "input"))
    )
    (net (code "144") (name "unconnected-(XB1-~{RESET}-Pad5)") (class "Default")
      (node (ref "XB1") (pin "5") (pinfunction "~{RESET}_5") (pintype "input"))
    )
    (net (code "145") (name "unconnected-(XB1-~{RTS}{slash}DIO6-Pad16)") (class "Default")
      (node (ref "XB1") (pin "16") (pinfunction "~{RTS}/DIO6_16") (pintype "bidirectional"))
    )
  )
)
